# mb_01.net
KiCad netlist of a schematic drawn in EAGLE
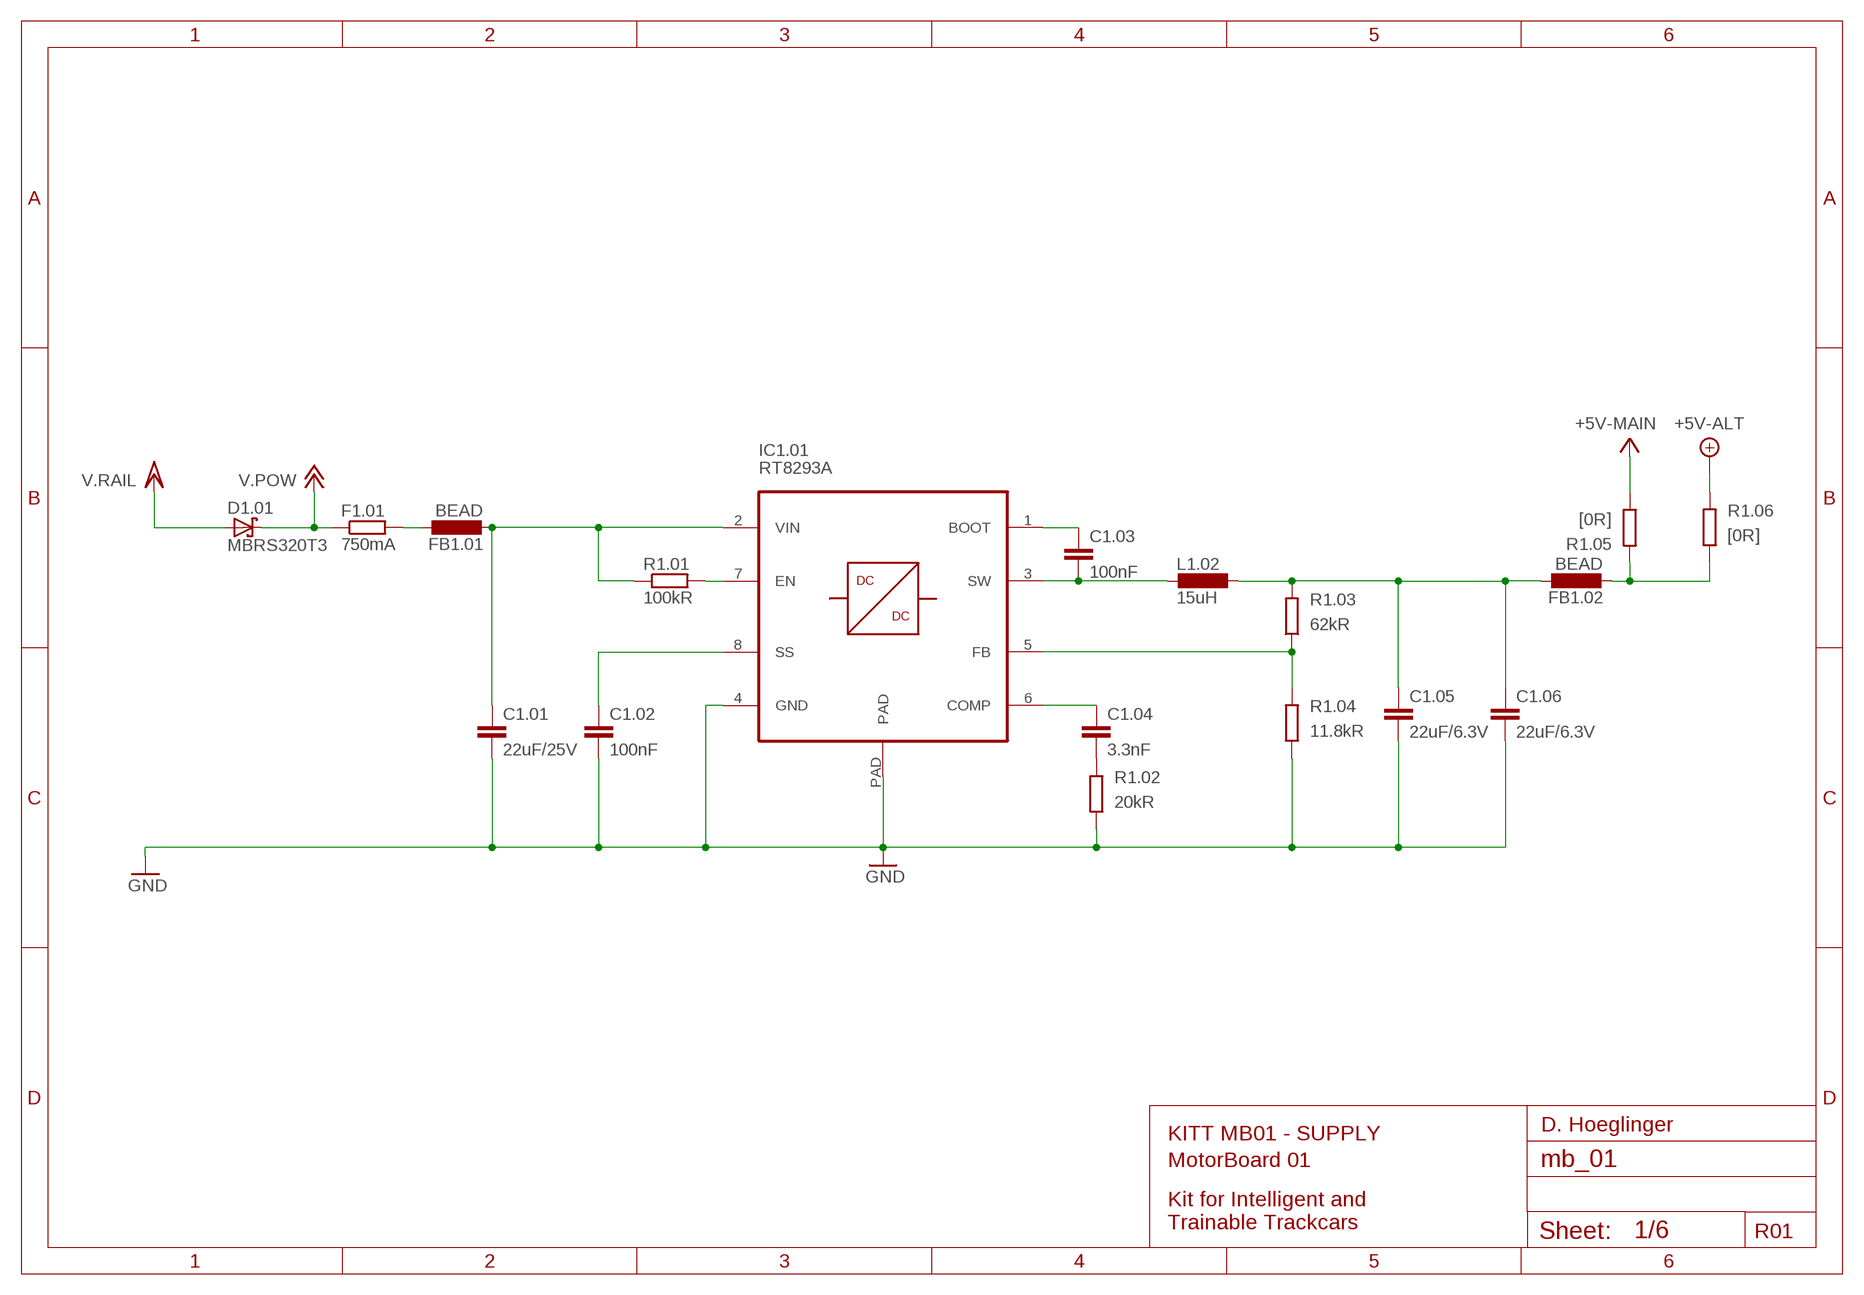
[diagram p0: schematic, sheet 1]
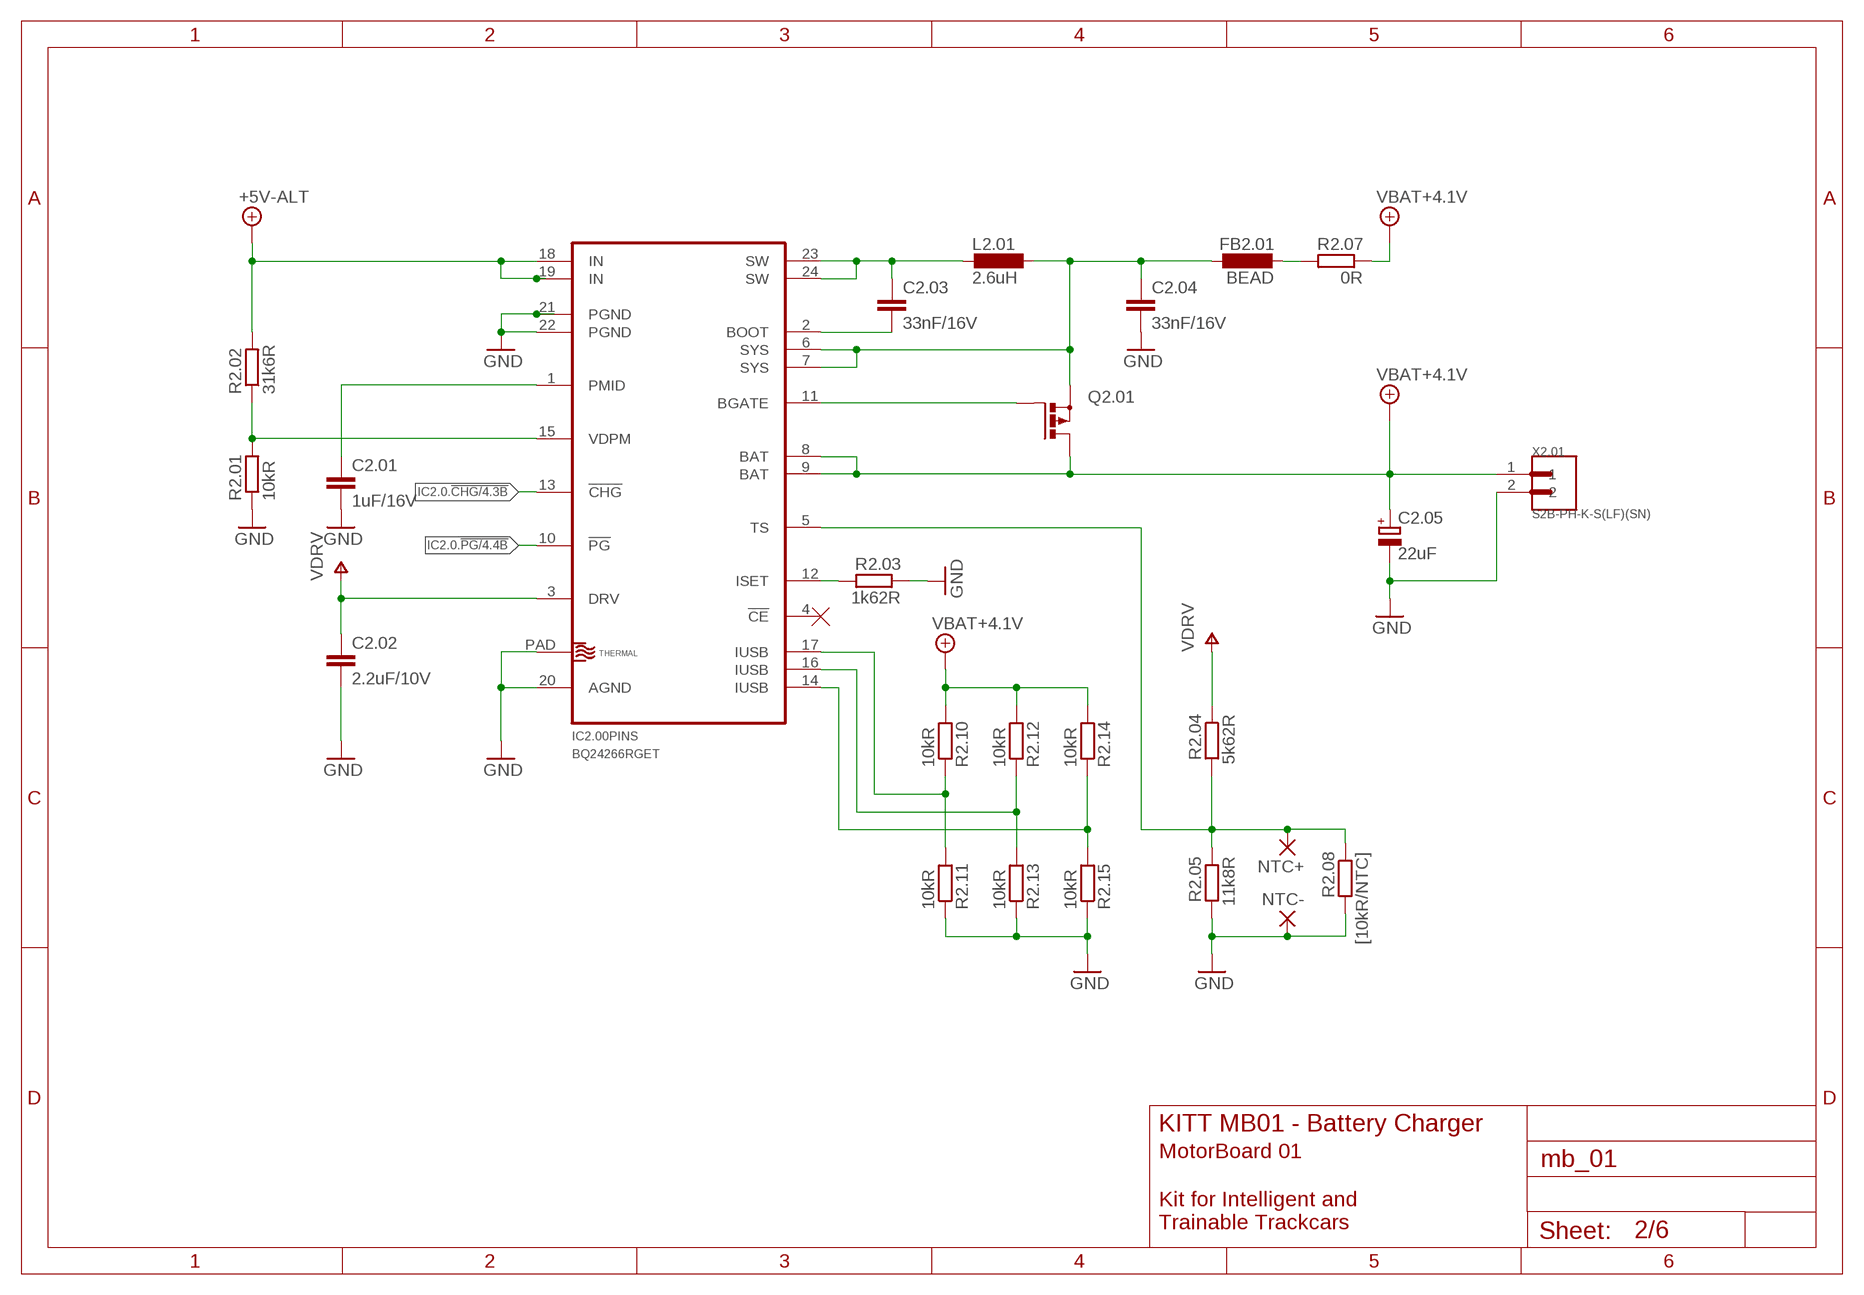
[diagram p1: schematic, sheet 2]
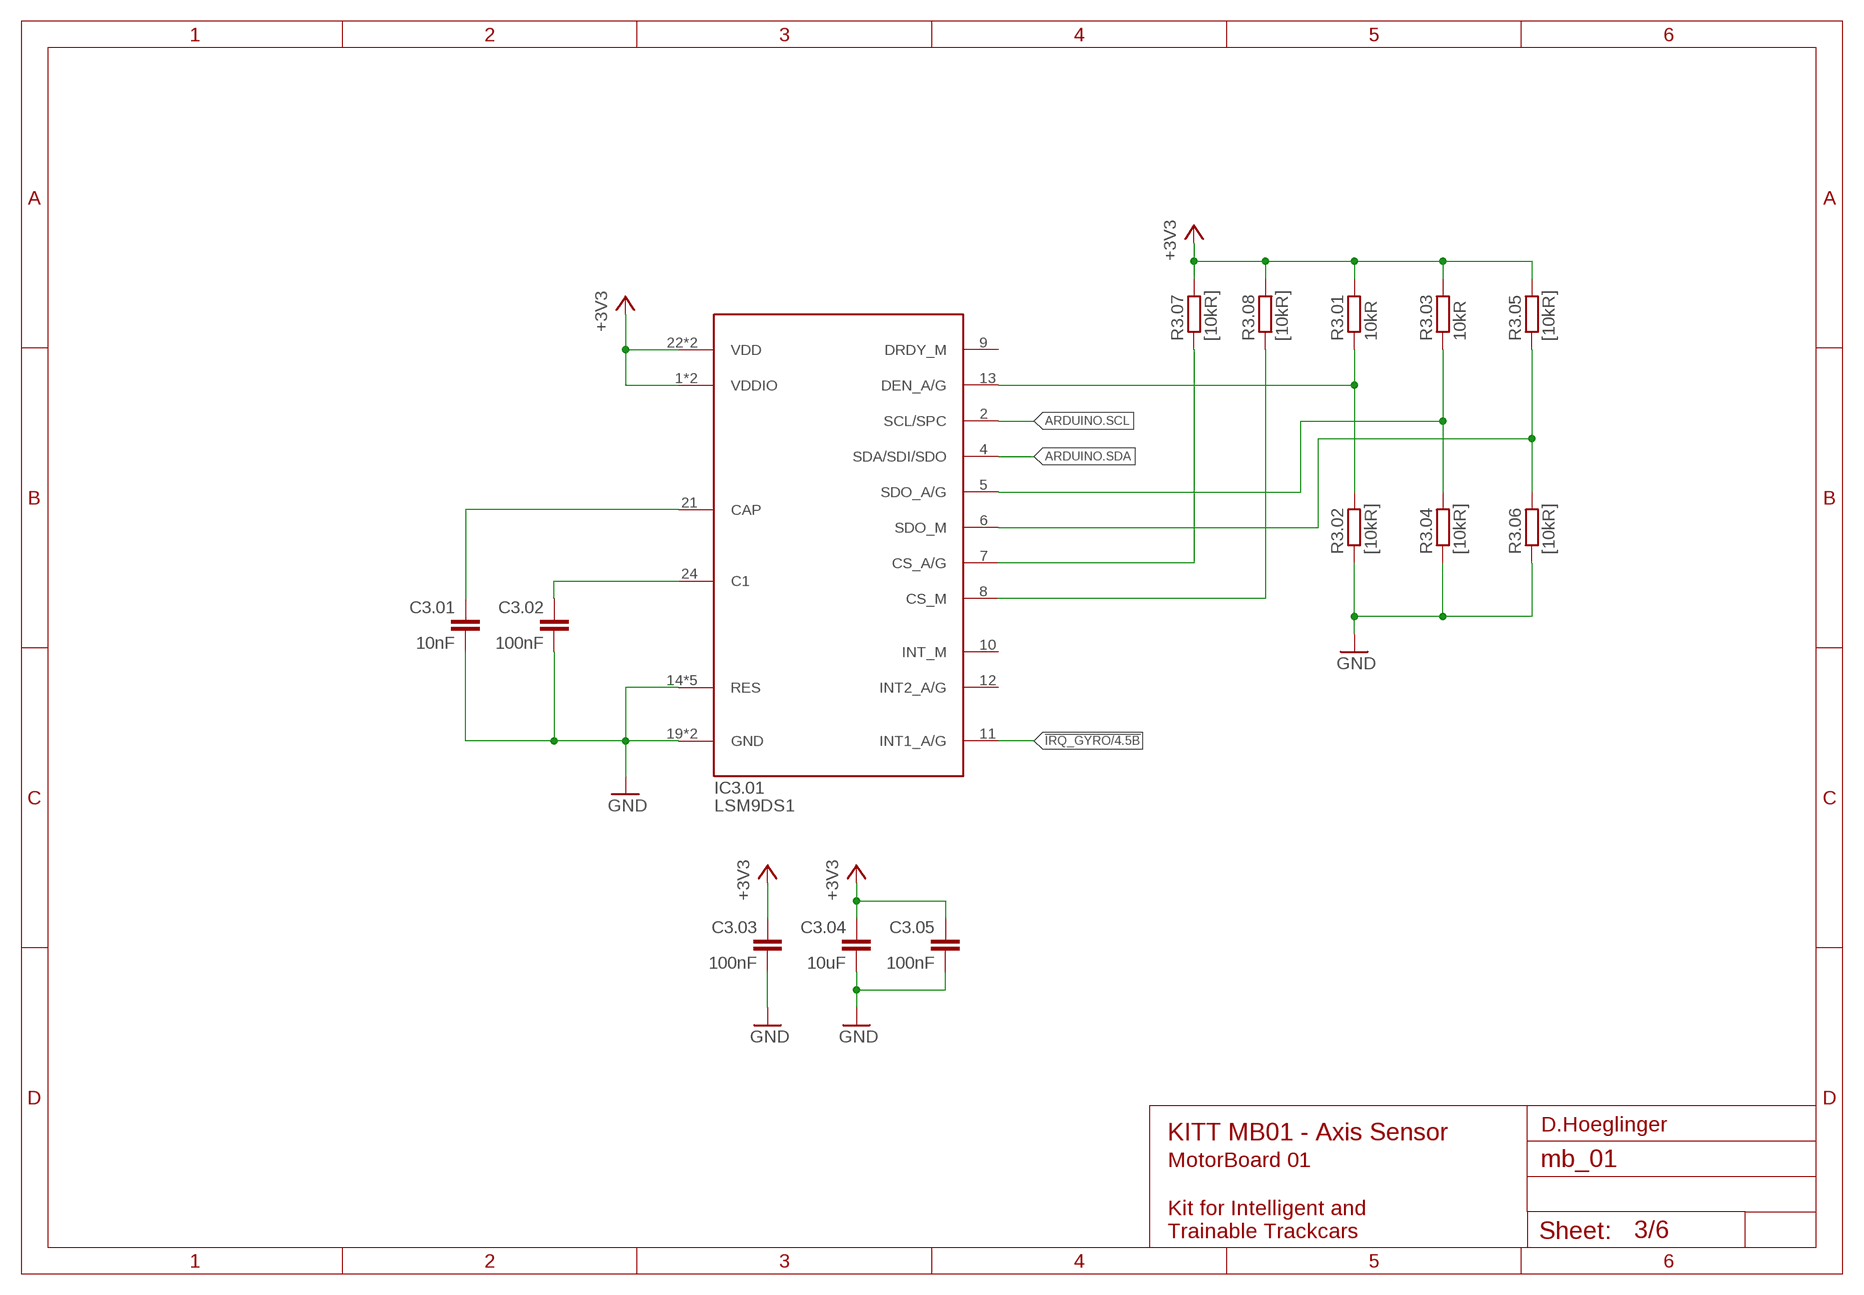
[diagram p2: schematic, sheet 3]
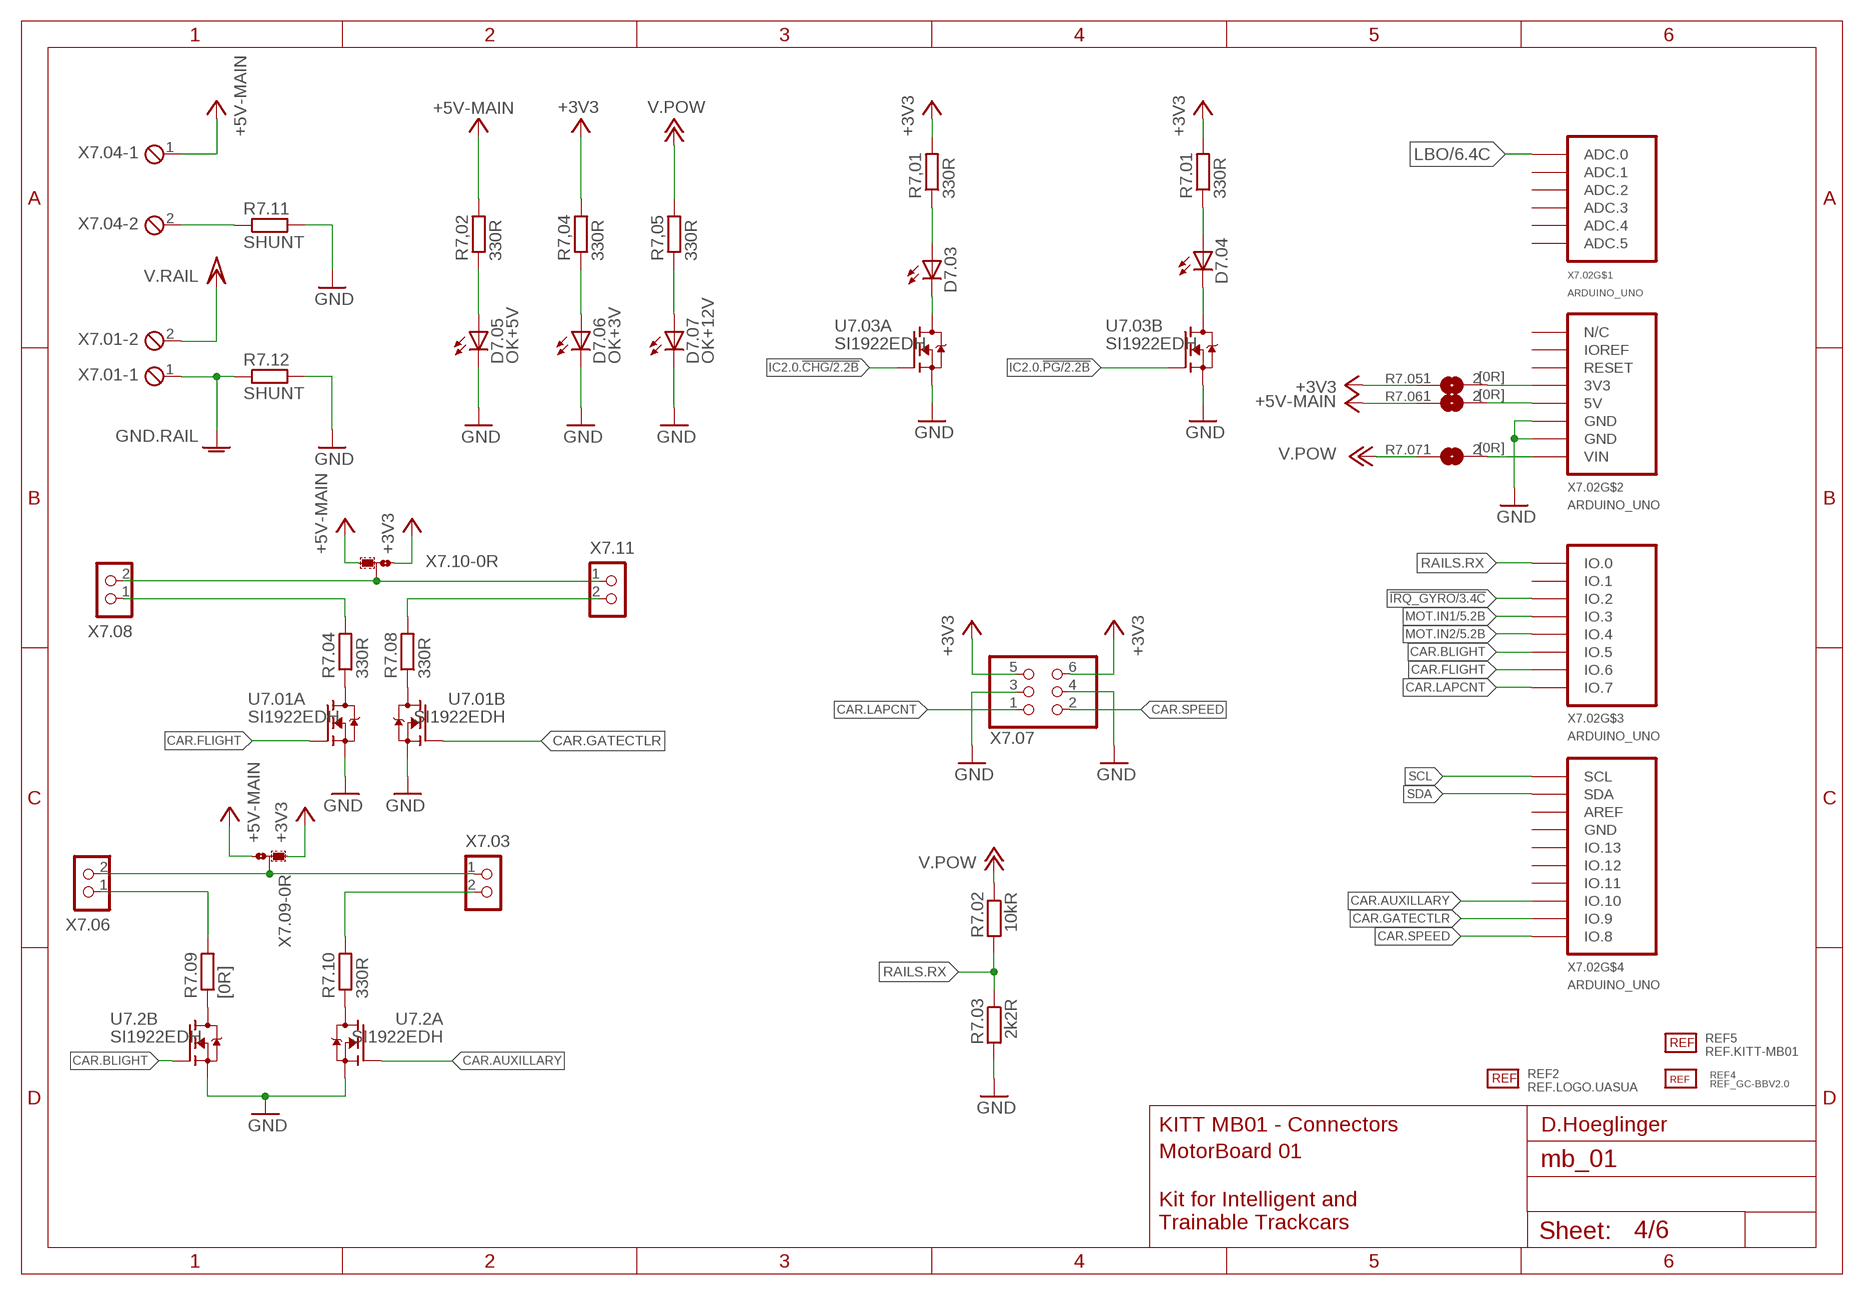
[diagram p3: schematic, sheet 4]
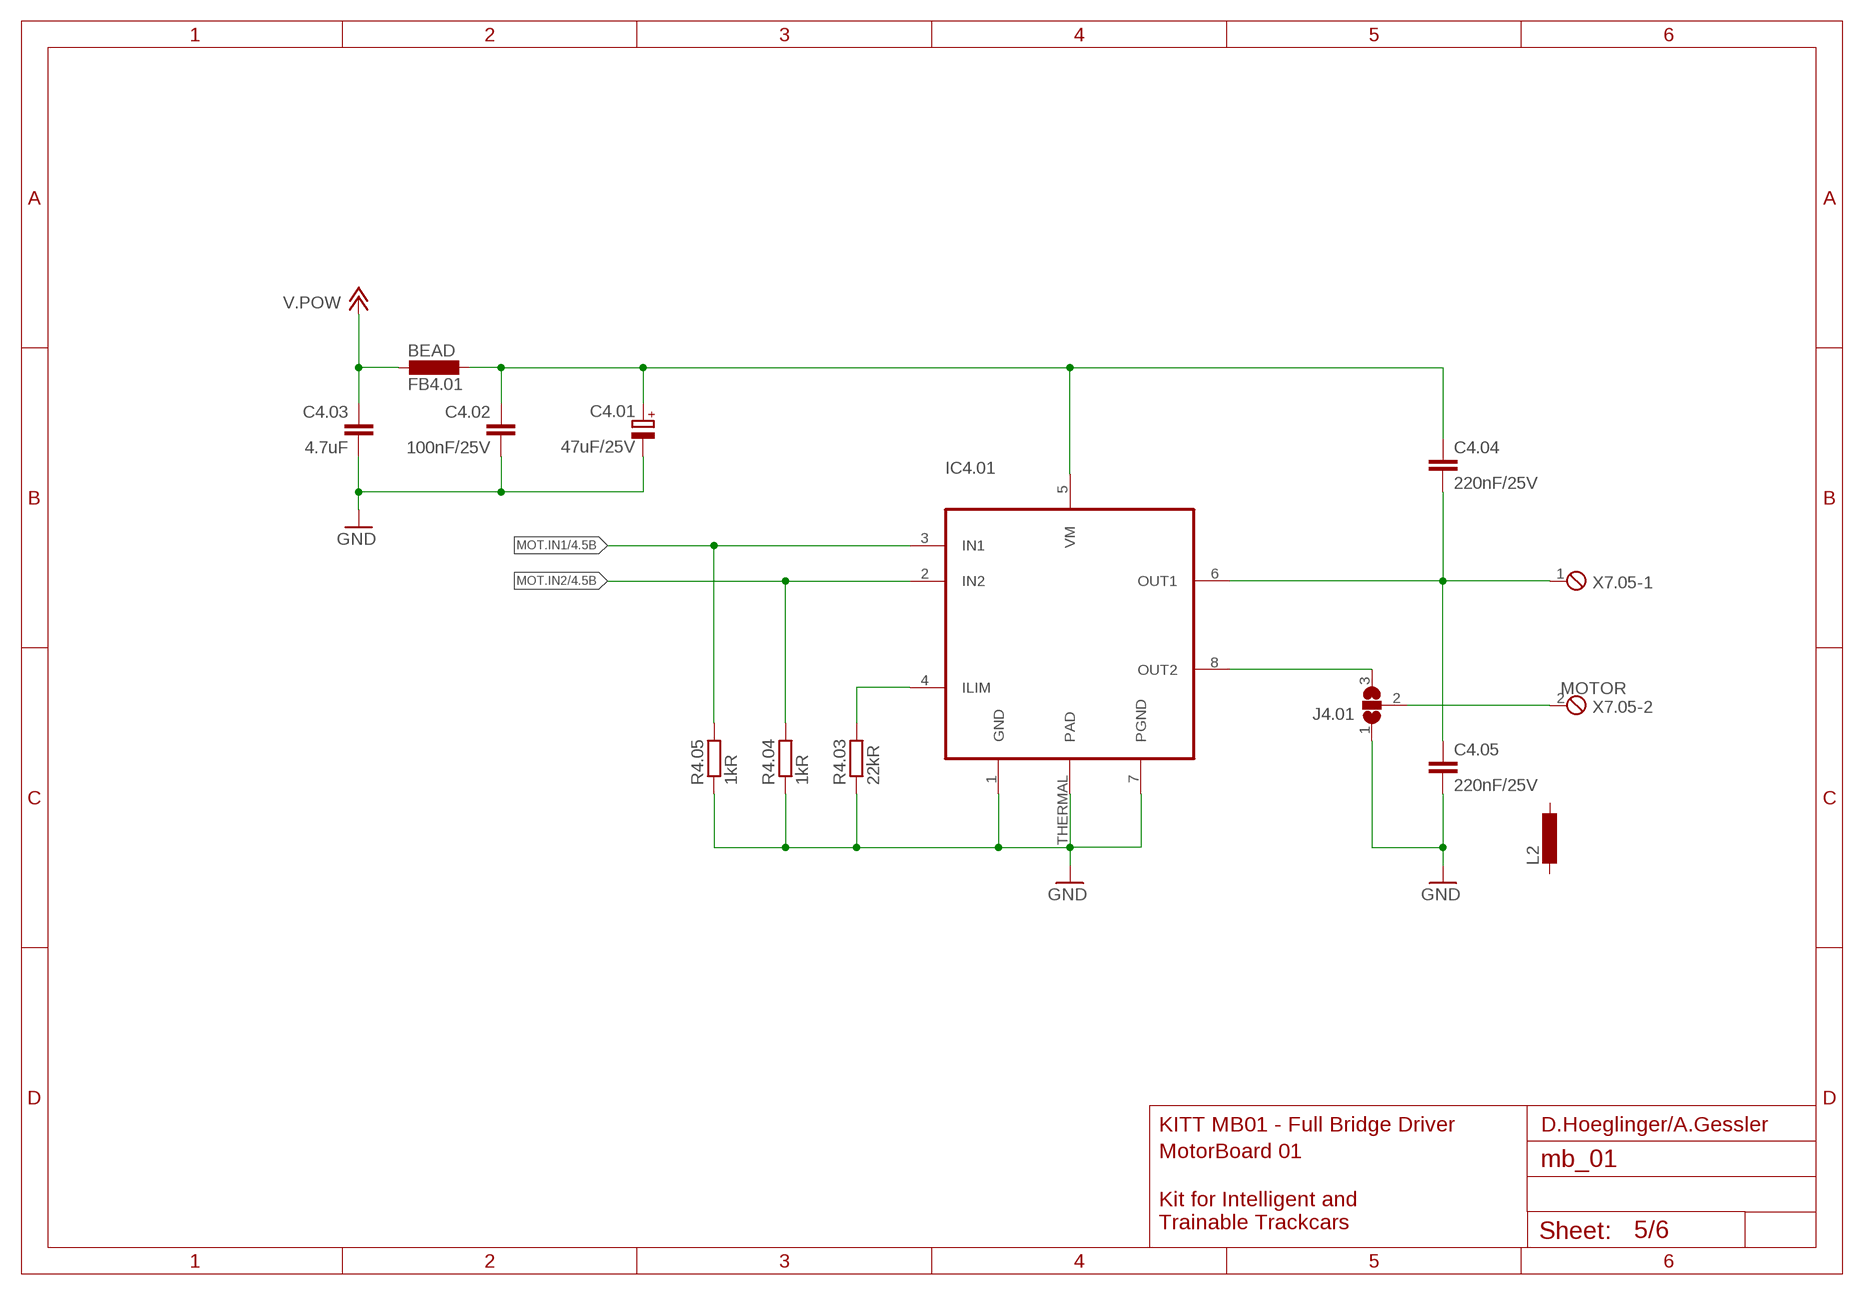
[diagram p4: schematic, sheet 5]
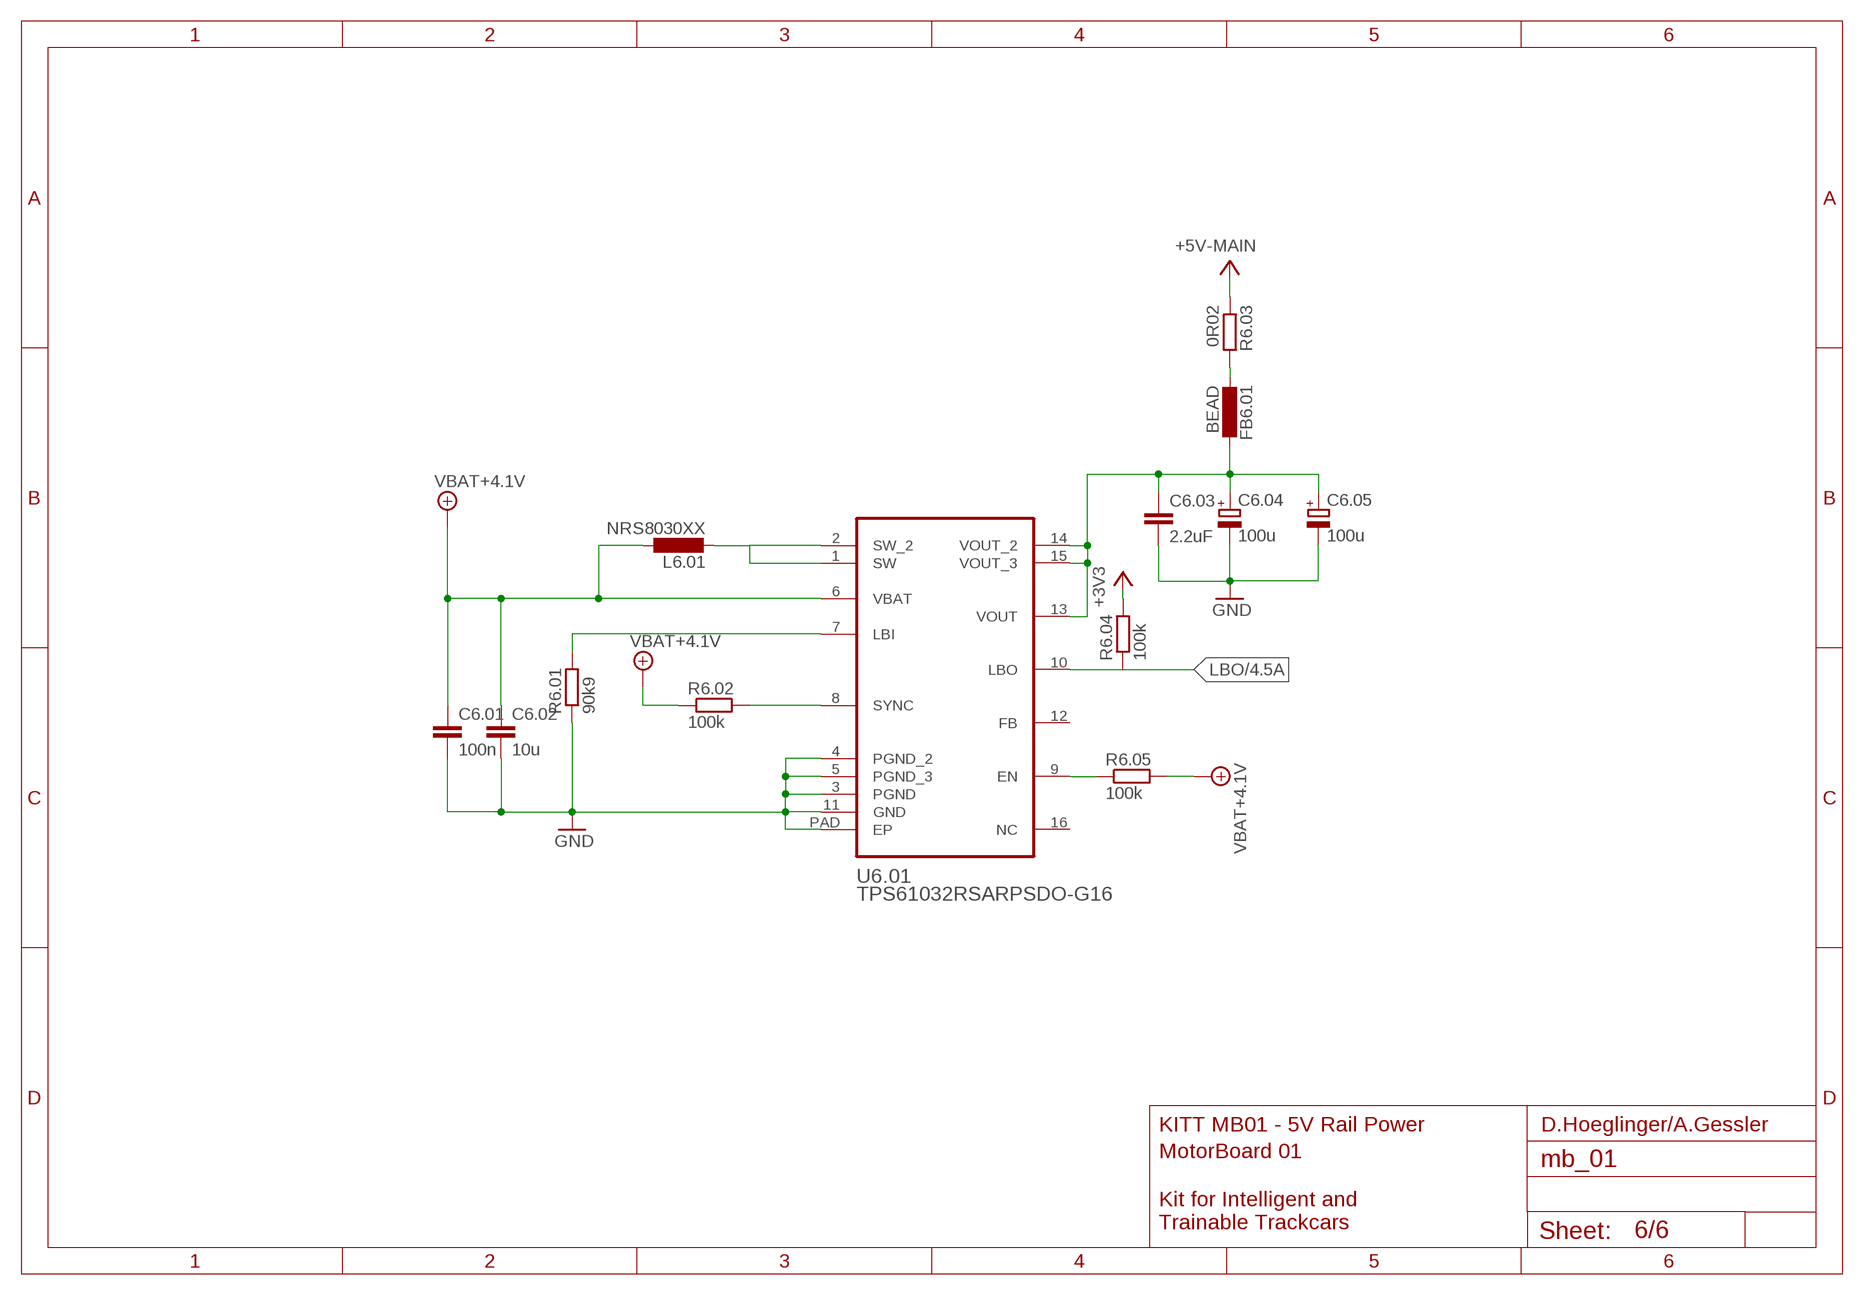
[diagram p5: schematic, sheet 6]

(export (version "E")
  (design (tool "Eeschema 10.0.6"))
  (components
    (comp (ref "C1.01")
      (value "22uF/25V")
      (footprint "eagle-import:C1210K")
      (libsource (lib "eagle-import") (part "C-EUC1210K"))
    )
    (comp (ref "C1.02")
      (value "100nF")
      (footprint "eagle-import:C0402K")
      (libsource (lib "eagle-import") (part "C-EUC0402K"))
    )
    (comp (ref "C1.03")
      (value "100nF")
      (footprint "eagle-import:C0402K")
      (libsource (lib "eagle-import") (part "C-EUC0402K"))
    )
    (comp (ref "C1.04")
      (value "3.3nF")
      (footprint "eagle-import:C0402K")
      (libsource (lib "eagle-import") (part "C-EUC0402K"))
    )
    (comp (ref "C1.05")
      (value "22uF/6.3V")
      (footprint "eagle-import:C1206K")
      (libsource (lib "eagle-import") (part "C-EUC1206K"))
    )
    (comp (ref "C1.06")
      (value "22uF/6.3V")
      (footprint "eagle-import:C1206K")
      (libsource (lib "eagle-import") (part "C-EUC1206K"))
    )
    (comp (ref "D1.01")
      (value "MBRS320T3")
      (footprint "eagle-import:SMC")
      (libsource (lib "eagle-import") (part "MBRS30T32"))
    )
    (comp (ref "F1.01")
      (value "750mA")
      (footprint "eagle-import:R1210")
      (libsource (lib "eagle-import") (part "R-EU_R1210"))
    )
    (comp (ref "FB1.01")
      (value "BEAD")
      (footprint "eagle-import:L4516C")
      (libsource (lib "eagle-import") (part "L-EUL4516C"))
    )
    (comp (ref "FB1.02")
      (value "BEAD")
      (footprint "eagle-import:L4516C")
      (libsource (lib "eagle-import") (part "L-EUL4516C"))
    )
    (comp (ref "IC1.01")
      (value "RT8293A")
      (footprint "eagle-import:SOIC-8-PAD")
      (libsource (lib "eagle-import") (part "RT8293A"))
    )
    (comp (ref "L1.02")
      (value "15uH")
      (footprint "eagle-import:TAIYO-YUDEN.NRS8030T4R7MJGJ")
      (libsource (lib "eagle-import") (part "NRS8030XX"))
    )
    (comp (ref "R1.01")
      (value "100kR")
      (footprint "eagle-import:R0402")
      (libsource (lib "eagle-import") (part "R-EU_R0402"))
    )
    (comp (ref "R1.02")
      (value "20kR")
      (footprint "eagle-import:R0402")
      (libsource (lib "eagle-import") (part "R-EU_R0402"))
    )
    (comp (ref "R1.03")
      (value "62kR")
      (footprint "eagle-import:R0402")
      (libsource (lib "eagle-import") (part "R-EU_R0402"))
    )
    (comp (ref "R1.04")
      (value "11.8kR")
      (footprint "eagle-import:R0402")
      (libsource (lib "eagle-import") (part "R-EU_R0402"))
    )
    (comp (ref "R1.05")
      (value "[0R]")
      (footprint "eagle-import:R0402")
      (libsource (lib "eagle-import") (part "R-EU_R0402"))
    )
    (comp (ref "R1.06")
      (value "[0R]")
      (footprint "eagle-import:R0402")
      (libsource (lib "eagle-import") (part "R-EU_R0402"))
    )
    (comp (ref "C2.01")
      (value "1uF/16V")
      (footprint "eagle-import:C0805")
      (libsource (lib "eagle-import") (part "C-EUC0805"))
    )
    (comp (ref "C2.02")
      (value "2.2uF/10V")
      (footprint "eagle-import:C0603K")
      (libsource (lib "eagle-import") (part "C-EUC0603K"))
    )
    (comp (ref "C2.03")
      (value "33nF/16V")
      (footprint "eagle-import:C0603")
      (libsource (lib "eagle-import") (part "C-EUC0603"))
    )
    (comp (ref "C2.04")
      (value "33nF/16V")
      (footprint "eagle-import:C0805")
      (libsource (lib "eagle-import") (part "C-EUC0805"))
    )
    (comp (ref "C2.05")
      (value "22uF")
      (footprint "eagle-import:A_3216-18R")
      (libsource (lib "eagle-import") (part "CPOL-EUA/3216-18R"))
    )
    (comp (ref "FB2.01")
      (value "BEAD")
      (footprint "eagle-import:L4516C")
      (libsource (lib "eagle-import") (part "L-EUL4516C"))
    )
    (comp (ref "IC2.00")
      (value "BQ24266RGET")
      (footprint "eagle-import:VQFN-24")
      (libsource (lib "eagle-import") (part "BQ24266RGET"))
    )
    (comp (ref "L2.01")
      (value "2.6uH")
      (footprint "eagle-import:TAIYO-YUDEN.NRS8030T4R7MJGJ")
      (libsource (lib "eagle-import") (part "NRS8030XX"))
    )
    (comp (ref "NTC+")
      (value "SMD2")
      (footprint "eagle-import:SMD1,27-2,54")
      (libsource (lib "eagle-import") (part "SMD2"))
    )
    (comp (ref "NTC-")
      (value "SMD2")
      (footprint "eagle-import:SMD1,27-2,54")
      (libsource (lib "eagle-import") (part "SMD2"))
    )
    (comp (ref "Q2.01")
      (value "P-MOSFET-SO8")
      (footprint "eagle-import:SO-08")
      (libsource (lib "eagle-import") (part "P-MOSFET-SO8"))
    )
    (comp (ref "R2.01")
      (value "10kR")
      (footprint "eagle-import:R0402")
      (libsource (lib "eagle-import") (part "R-EU_R0402"))
    )
    (comp (ref "R2.02")
      (value "31k6R")
      (footprint "eagle-import:R0402")
      (libsource (lib "eagle-import") (part "R-EU_R0402"))
    )
    (comp (ref "R2.03")
      (value "1k62R")
      (footprint "eagle-import:R0402")
      (libsource (lib "eagle-import") (part "R-EU_R0402"))
    )
    (comp (ref "R2.04")
      (value "5k62R")
      (footprint "eagle-import:R0402")
      (libsource (lib "eagle-import") (part "R-EU_R0402"))
    )
    (comp (ref "R2.05")
      (value "11k8R")
      (footprint "eagle-import:R0402")
      (libsource (lib "eagle-import") (part "R-EU_R0402"))
    )
    (comp (ref "R2.07")
      (value "0R")
      (footprint "eagle-import:R0402")
      (libsource (lib "eagle-import") (part "R-EU_R0402"))
    )
    (comp (ref "R2.08")
      (value "[10kR/NTC]")
      (footprint "eagle-import:R0402")
      (libsource (lib "eagle-import") (part "R-EU_R0402"))
    )
    (comp (ref "R2.10")
      (value "10kR")
      (footprint "eagle-import:R0402")
      (libsource (lib "eagle-import") (part "R-EU_R0402"))
    )
    (comp (ref "R2.11")
      (value "10kR")
      (footprint "eagle-import:R0402")
      (libsource (lib "eagle-import") (part "R-EU_R0402"))
    )
    (comp (ref "R2.12")
      (value "10kR")
      (footprint "eagle-import:R0402")
      (libsource (lib "eagle-import") (part "R-EU_R0402"))
    )
    (comp (ref "R2.13")
      (value "10kR")
      (footprint "eagle-import:R0402")
      (libsource (lib "eagle-import") (part "R-EU_R0402"))
    )
    (comp (ref "R2.14")
      (value "10kR")
      (footprint "eagle-import:R0402")
      (libsource (lib "eagle-import") (part "R-EU_R0402"))
    )
    (comp (ref "R2.15")
      (value "10kR")
      (footprint "eagle-import:R0402")
      (libsource (lib "eagle-import") (part "R-EU_R0402"))
    )
    (comp (ref "X2.01")
      (value "S2B-PH-K-S(LF)(SN)")
      (footprint "eagle-import:JST_S2B-PH-K-S(LF)(SN)")
      (fields (field (name "MF") "JST"))
      (libsource (lib "eagle-import") (part "S2B-PH-K-S(LF)(SN)"))
    )
    (comp (ref "D7.03")
      (value "LEDCHIPLED_1206")
      (footprint "eagle-import:CHIPLED_1206")
      (libsource (lib "eagle-import") (part "LEDCHIPLED_1206"))
    )
    (comp (ref "D7.04")
      (value "LEDCHIPLED_1206")
      (footprint "eagle-import:CHIPLED_1206")
      (libsource (lib "eagle-import") (part "LEDCHIPLED_1206"))
    )
    (comp (ref "D7.05")
      (value "OK+5V")
      (footprint "eagle-import:CHIPLED_1206")
      (libsource (lib "eagle-import") (part "LEDCHIPLED_1206"))
    )
    (comp (ref "D7.06")
      (value "OK+3V")
      (footprint "eagle-import:CHIPLED_1206")
      (libsource (lib "eagle-import") (part "LEDCHIPLED_1206"))
    )
    (comp (ref "D7.07")
      (value "OK+12V")
      (footprint "eagle-import:CHIPLED_1206")
      (libsource (lib "eagle-import") (part "LEDCHIPLED_1206"))
    )
    (comp (ref "R7,01")
      (value "330R")
      (footprint "eagle-import:R0603")
      (libsource (lib "eagle-import") (part "R-EU_R0603"))
    )
    (comp (ref "R7,02")
      (value "330R")
      (footprint "eagle-import:R0603")
      (libsource (lib "eagle-import") (part "R-EU_R0603"))
    )
    (comp (ref "R7,04")
      (value "330R")
      (footprint "eagle-import:R0603")
      (libsource (lib "eagle-import") (part "R-EU_R0603"))
    )
    (comp (ref "R7,05")
      (value "330R")
      (footprint "eagle-import:R0603")
      (libsource (lib "eagle-import") (part "R-EU_R0603"))
    )
    (comp (ref "R7.01")
      (value "330R")
      (footprint "eagle-import:R0603")
      (libsource (lib "eagle-import") (part "R-EU_R0603"))
    )
    (comp (ref "R7.02")
      (value "10kR")
      (footprint "eagle-import:M0805")
      (libsource (lib "eagle-import") (part "R-EU_M0805"))
    )
    (comp (ref "R7.03")
      (value "2k2R")
      (footprint "eagle-import:M0805")
      (libsource (lib "eagle-import") (part "R-EU_M0805"))
    )
    (comp (ref "R7.04")
      (value "330R")
      (footprint "eagle-import:R0603")
      (libsource (lib "eagle-import") (part "R-EU_R0603"))
    )
    (comp (ref "R7.05")
      (value "[0R]")
      (footprint "eagle-import:SJ")
      (libsource (lib "eagle-import") (part "SJ"))
    )
    (comp (ref "R7.06")
      (value "[0R]")
      (footprint "eagle-import:SJ")
      (libsource (lib "eagle-import") (part "SJ"))
    )
    (comp (ref "R7.07")
      (value "[0R]")
      (footprint "eagle-import:SJ")
      (libsource (lib "eagle-import") (part "SJ"))
    )
    (comp (ref "R7.08")
      (value "330R")
      (footprint "eagle-import:R0603")
      (libsource (lib "eagle-import") (part "R-EU_R0603"))
    )
    (comp (ref "R7.09")
      (value "[0R]")
      (footprint "eagle-import:R0603")
      (libsource (lib "eagle-import") (part "R-EU_R0603"))
    )
    (comp (ref "R7.10")
      (value "330R")
      (footprint "eagle-import:R0603")
      (libsource (lib "eagle-import") (part "R-EU_R0603"))
    )
    (comp (ref "R7.11")
      (value "SHUNT")
      (footprint "eagle-import:R1206")
      (libsource (lib "eagle-import") (part "R-EU_R1206"))
    )
    (comp (ref "R7.12")
      (value "SHUNT")
      (footprint "eagle-import:R1206")
      (libsource (lib "eagle-import") (part "R-EU_R1206"))
    )
    (comp (ref "REF2")
      (value "REF.LOGO.UASUA")
      (footprint "eagle-import:REF_LOGO_UASUA")
      (libsource (lib "eagle-import") (part "REF.LOGO.UASUA"))
    )
    (comp (ref "REF4")
      (value "REF_GC-BBV2.0")
      (footprint "eagle-import:REF_GHOSTCAR")
      (libsource (lib "eagle-import") (part "REF_GC-BBV2.0"))
    )
    (comp (ref "REF5")
      (value "REF.KITT-MB01")
      (footprint "eagle-import:REF_KITT_MB01")
      (libsource (lib "eagle-import") (part "REF.KITT-MB01"))
    )
    (comp (ref "U7.01")
      (value "SI1922EDH")
      (footprint "eagle-import:SC70-6")
      (libsource (lib "eagle-import") (part "SI1922EDH"))
    )
    (comp (ref "U7.2")
      (value "SI1922EDH")
      (footprint "eagle-import:SC70-6")
      (libsource (lib "eagle-import") (part "SI1922EDH"))
    )
    (comp (ref "U7.03")
      (value "SI1922EDH")
      (footprint "eagle-import:SC70-6")
      (libsource (lib "eagle-import") (part "SI1922EDH"))
    )
    (comp (ref "X7.01")
      (value "MPT2")
      (footprint "eagle-import:2POL254")
      (libsource (lib "eagle-import") (part "MPT2"))
    )
    (comp (ref "X7.02")
      (value "ARDUINO_UNO")
      (footprint "eagle-import:AU_PINS")
      (libsource (lib "eagle-import") (part "ARDUINO_UNO"))
    )
    (comp (ref "X7.03")
      (value "CON_HEADER_1X02")
      (footprint "eagle-import:M1X2_MALE_RIGHT_ANGLED_SMD")
      (libsource (lib "eagle-import") (part "CON_HEADER_1X02"))
    )
    (comp (ref "X7.04")
      (value "MPT2")
      (footprint "eagle-import:2POL254")
      (libsource (lib "eagle-import") (part "MPT2"))
    )
    (comp (ref "X7.06")
      (value "CON_HEADER_1X02")
      (footprint "eagle-import:M1X2_MALE_RIGHT_ANGLED_SMD")
      (libsource (lib "eagle-import") (part "CON_HEADER_1X02"))
    )
    (comp (ref "X7.07")
      (value "PINHD-2X3/90")
      (footprint "eagle-import:2X03_90")
      (libsource (lib "eagle-import") (part "PINHD-2X3/90"))
    )
    (comp (ref "X7.08")
      (value "CON_HEADER_1X02")
      (footprint "eagle-import:M1X2_MALE_RIGHT_ANGLED_SMD")
      (libsource (lib "eagle-import") (part "CON_HEADER_1X02"))
    )
    (comp (ref "X7.09")
      (value "0R-JUMPA")
      (footprint "eagle-import:A0R-JMP")
      (libsource (lib "eagle-import") (part "0R-JUMPA"))
    )
    (comp (ref "X7.10")
      (value "0R-JUMPA")
      (footprint "eagle-import:A0R-JMP")
      (libsource (lib "eagle-import") (part "0R-JUMPA"))
    )
    (comp (ref "X7.11")
      (value "CON_HEADER_1X02")
      (footprint "eagle-import:M1X2_MALE_RIGHT_ANGLED_SMD")
      (libsource (lib "eagle-import") (part "CON_HEADER_1X02"))
    )
    (comp (ref "C3.01")
      (value "10nF")
      (footprint "eagle-import:C0603")
      (libsource (lib "eagle-import") (part "C-EUC0603"))
    )
    (comp (ref "C3.02")
      (value "100nF")
      (footprint "eagle-import:C0402")
      (libsource (lib "eagle-import") (part "C-EUC0402"))
    )
    (comp (ref "C3.03")
      (value "100nF")
      (footprint "eagle-import:C0402")
      (libsource (lib "eagle-import") (part "C-EUC0402"))
    )
    (comp (ref "C3.04")
      (value "10uF")
      (footprint "eagle-import:C0603K")
      (libsource (lib "eagle-import") (part "resistor_C-EUC0603K"))
    )
    (comp (ref "C3.05")
      (value "100nF")
      (footprint "eagle-import:C0402")
      (libsource (lib "eagle-import") (part "C-EUC0402"))
    )
    (comp (ref "IC3.01")
      (value "LSM9DS1")
      (footprint "eagle-import:LGA-24")
      (fields (field (name "MF") "STMicroelectronics"))
      (libsource (lib "eagle-import") (part "LSM9DS1"))
    )
    (comp (ref "R3.01")
      (value "10kR")
      (footprint "eagle-import:R0402")
      (libsource (lib "eagle-import") (part "R-EU_R0402"))
    )
    (comp (ref "R3.02")
      (value "[10kR]")
      (footprint "eagle-import:R0402")
      (libsource (lib "eagle-import") (part "R-EU_R0402"))
    )
    (comp (ref "R3.03")
      (value "10kR")
      (footprint "eagle-import:R0402")
      (libsource (lib "eagle-import") (part "R-EU_R0402"))
    )
    (comp (ref "R3.04")
      (value "[10kR]")
      (footprint "eagle-import:R0402")
      (libsource (lib "eagle-import") (part "R-EU_R0402"))
    )
    (comp (ref "R3.05")
      (value "[10kR]")
      (footprint "eagle-import:R0402")
      (libsource (lib "eagle-import") (part "R-EU_R0402"))
    )
    (comp (ref "R3.06")
      (value "[10kR]")
      (footprint "eagle-import:R0402")
      (libsource (lib "eagle-import") (part "R-EU_R0402"))
    )
    (comp (ref "R3.07")
      (value "[10kR]")
      (footprint "eagle-import:R0402")
      (libsource (lib "eagle-import") (part "R-EU_R0402"))
    )
    (comp (ref "R3.08")
      (value "[10kR]")
      (footprint "eagle-import:R0402")
      (libsource (lib "eagle-import") (part "R-EU_R0402"))
    )
    (comp (ref "C6.01")
      (value "100n")
      (footprint "eagle-import:C0402")
      (libsource (lib "eagle-import") (part "C-EUC0402"))
    )
    (comp (ref "C6.02")
      (value "10u")
      (footprint "eagle-import:C0603")
      (libsource (lib "eagle-import") (part "C-EUC0603"))
    )
    (comp (ref "C6.03")
      (value "2.2uF")
      (footprint "eagle-import:C0603")
      (libsource (lib "eagle-import") (part "C-EUC0603"))
    )
    (comp (ref "C6.04")
      (value "100u")
      (footprint "eagle-import:C-2312")
      (libsource (lib "eagle-import") (part "CPOL-29172312"))
    )
    (comp (ref "C6.05")
      (value "100u")
      (footprint "eagle-import:C-2312")
      (libsource (lib "eagle-import") (part "CPOL-29172312"))
    )
    (comp (ref "FB6.01")
      (value "BEAD")
      (footprint "eagle-import:L4516C")
      (libsource (lib "eagle-import") (part "L-EUL4516C"))
    )
    (comp (ref "L6.01")
      (value "NRS8030XX")
      (footprint "eagle-import:TAIYO-YUDEN.NRS8030T4R7MJGJ")
      (libsource (lib "eagle-import") (part "NRS8030XX"))
    )
    (comp (ref "R6.01")
      (value "90k9")
      (footprint "eagle-import:R0402")
      (libsource (lib "eagle-import") (part "R-EU_R0402"))
    )
    (comp (ref "R6.02")
      (value "100k")
      (footprint "eagle-import:R0402")
      (libsource (lib "eagle-import") (part "R-EU_R0402"))
    )
    (comp (ref "R6.03")
      (value "0R02")
      (footprint "eagle-import:R0805")
      (libsource (lib "eagle-import") (part "R-EU_R0805"))
    )
    (comp (ref "R6.04")
      (value "100k")
      (footprint "eagle-import:R0402")
      (libsource (lib "eagle-import") (part "R-EU_R0402"))
    )
    (comp (ref "R6.05")
      (value "100k")
      (footprint "eagle-import:R0402")
      (libsource (lib "eagle-import") (part "R-EU_R0402"))
    )
    (comp (ref "U6.01")
      (value "TPS61032RSARPSDO-G16")
      (footprint "eagle-import:R-PDSO-G16")
      (libsource (lib "eagle-import") (part "TPS61032RSARPSDO-G16"))
    )
    (comp (ref "C4.01")
      (value "47uF/25V")
      (footprint "eagle-import:C_6032-28R")
      (libsource (lib "eagle-import") (part "CPOL-EUC/6032-28R"))
    )
    (comp (ref "C4.02")
      (value "100nF/25V")
      (footprint "eagle-import:C0603K")
      (libsource (lib "eagle-import") (part "resistor_C-EUC0603K"))
    )
    (comp (ref "C4.03")
      (value "4.7uF")
      (footprint "eagle-import:C0805K")
      (libsource (lib "eagle-import") (part "resistor_C-EUC0805K"))
    )
    (comp (ref "C4.04")
      (value "220nF/25V")
      (footprint "eagle-import:C0603K")
      (libsource (lib "eagle-import") (part "C-EUC0603K"))
    )
    (comp (ref "C4.05")
      (value "220nF/25V")
      (footprint "eagle-import:C0603K")
      (libsource (lib "eagle-import") (part "C-EUC0603K"))
    )
    (comp (ref "FB4.01")
      (value "BEAD")
      (footprint "eagle-import:L4516C")
      (libsource (lib "eagle-import") (part "L-EUL4516C"))
    )
    (comp (ref "IC4.01")
      (value "DRV8871")
      (footprint "eagle-import:HSOP8")
      (libsource (lib "eagle-import") (part "DRV8871"))
    )
    (comp (ref "J4.01")
      (value "SJ2W")
      (footprint "eagle-import:SJ_2")
      (libsource (lib "eagle-import") (part "SJ2W"))
    )
    (comp (ref "L2")
      (value "L-EUL4516C")
      (footprint "eagle-import:L4516C")
      (libsource (lib "eagle-import") (part "L-EUL4516C"))
    )
    (comp (ref "R4.03")
      (value "22kR")
      (footprint "eagle-import:R0402")
      (libsource (lib "eagle-import") (part "resistor_R-EU_R0402"))
    )
    (comp (ref "R4.04")
      (value "1kR")
      (footprint "eagle-import:R0402")
      (libsource (lib "eagle-import") (part "resistor_R-EU_R0402"))
    )
    (comp (ref "R4.05")
      (value "1kR")
      (footprint "eagle-import:R0402")
      (libsource (lib "eagle-import") (part "resistor_R-EU_R0402"))
    )
    (comp (ref "X7.05")
      (value "MOTOR")
      (footprint "eagle-import:2POL254")
      (libsource (lib "eagle-import") (part "MPT2"))
    )
  )
  (nets
    (net (code "1") (name "+3V3") (class "Default")
      (node (ref "C3.03") (pin "1") (pinfunction "1_1") (pintype "passive"))
      (node (ref "C3.04") (pin "1") (pinfunction "1_1") (pintype "passive"))
      (node (ref "C3.05") (pin "1") (pinfunction "1_1") (pintype "passive"))
      (node (ref "IC3.01") (pin "1") (pinfunction "VDDIO_1") (pintype "bidirectional"))
      (node (ref "IC3.01") (pin "22") (pinfunction "VDD_22") (pintype "bidirectional"))
      (node (ref "IC3.01") (pin "23") (pinfunction "VDD_23") (pintype "bidirectional"))
      (node (ref "IC3.01") (pin "3") (pinfunction "VDDIO_3") (pintype "bidirectional"))
      (node (ref "R3.01") (pin "2") (pinfunction "2_2") (pintype "passive"))
      (node (ref "R3.03") (pin "2") (pinfunction "2_2") (pintype "passive"))
      (node (ref "R3.05") (pin "2") (pinfunction "2_2") (pintype "passive"))
      (node (ref "R3.07") (pin "2") (pinfunction "2_2") (pintype "passive"))
      (node (ref "R3.08") (pin "2") (pinfunction "2_2") (pintype "passive"))
      (node (ref "R6.04") (pin "2") (pinfunction "2_2") (pintype "passive"))
      (node (ref "R7,01") (pin "2") (pinfunction "2_2") (pintype "passive"))
      (node (ref "R7,04") (pin "2") (pinfunction "2_2") (pintype "passive"))
      (node (ref "R7.01") (pin "2") (pinfunction "2_2") (pintype "passive"))
      (node (ref "R7.05") (pin "1") (pinfunction "1_1") (pintype "passive"))
      (node (ref "X7.07") (pin "5") (pinfunction "5_5") (pintype "passive"))
      (node (ref "X7.07") (pin "6") (pinfunction "6_6") (pintype "passive"))
      (node (ref "X7.09") (pin "1") (pinfunction "1_1") (pintype "passive"))
      (node (ref "X7.10") (pin "1") (pinfunction "1_1") (pintype "passive"))
    )
    (net (code "2") (name "+4.1V") (class "Default")
      (node (ref "C2.05") (pin "+") (pinfunction "+_+") (pintype "passive"))
      (node (ref "C6.01") (pin "1") (pinfunction "1_1") (pintype "passive"))
      (node (ref "C6.02") (pin "1") (pinfunction "1_1") (pintype "passive"))
      (node (ref "IC2.00") (pin "8") (pinfunction "BAT_8") (pintype "bidirectional"))
      (node (ref "IC2.00") (pin "9") (pinfunction "BAT_9") (pintype "bidirectional"))
      (node (ref "L6.01") (pin "1") (pinfunction "1_1") (pintype "passive"))
      (node (ref "Q2.01") (pin "5") (pinfunction "D_5") (pintype "passive"))
      (node (ref "Q2.01") (pin "6") (pinfunction "D_6") (pintype "passive"))
      (node (ref "Q2.01") (pin "7") (pinfunction "D_7") (pintype "passive"))
      (node (ref "Q2.01") (pin "8") (pinfunction "D_8") (pintype "passive"))
      (node (ref "R2.07") (pin "1") (pinfunction "1_1") (pintype "passive"))
      (node (ref "R2.10") (pin "2") (pinfunction "2_2") (pintype "passive"))
      (node (ref "R2.12") (pin "2") (pinfunction "2_2") (pintype "passive"))
      (node (ref "R2.14") (pin "2") (pinfunction "2_2") (pintype "passive"))
      (node (ref "R6.02") (pin "1") (pinfunction "1_1") (pintype "passive"))
      (node (ref "R6.05") (pin "2") (pinfunction "2_2") (pintype "passive"))
      (node (ref "U6.01") (pin "6") (pinfunction "VBAT_6") (pintype "input"))
      (node (ref "X2.01") (pin "1") (pinfunction "1_1") (pintype "passive"))
    )
    (net (code "3") (name "+5V") (class "Default")
      (node (ref "IC2.00") (pin "18") (pinfunction "IN_18") (pintype "bidirectional"))
      (node (ref "IC2.00") (pin "19") (pinfunction "IN_19") (pintype "bidirectional"))
      (node (ref "R1.05") (pin "1") (pinfunction "1_1") (pintype "passive"))
      (node (ref "R1.06") (pin "2") (pinfunction "2_2") (pintype "passive"))
      (node (ref "R2.02") (pin "2") (pinfunction "2_2") (pintype "passive"))
      (node (ref "R6.03") (pin "1") (pinfunction "1_1") (pintype "passive"))
      (node (ref "R7,02") (pin "2") (pinfunction "2_2") (pintype "passive"))
      (node (ref "R7.06") (pin "1") (pinfunction "1_1") (pintype "passive"))
      (node (ref "X7.04") (pin "1") (pinfunction "1_1") (pintype "passive"))
      (node (ref "X7.09") (pin "3") (pinfunction "3_3") (pintype "passive"))
      (node (ref "X7.10") (pin "3") (pinfunction "3_3") (pintype "passive"))
    )
    (net (code "4") (name "+12V") (class "Default")
      (node (ref "C4.03") (pin "1") (pinfunction "1_1") (pintype "passive"))
      (node (ref "D1.01") (pin "C") (pinfunction "C_C") (pintype "passive"))
      (node (ref "F1.01") (pin "1") (pinfunction "1_1") (pintype "passive"))
      (node (ref "FB4.01") (pin "2") (pinfunction "2_2") (pintype "passive"))
      (node (ref "R7,05") (pin "2") (pinfunction "2_2") (pintype "passive"))
      (node (ref "R7.02") (pin "1") (pinfunction "1_1") (pintype "passive"))
      (node (ref "R7.07") (pin "1") (pinfunction "1_1") (pintype "passive"))
    )
    (net (code "5") (name "ARDUINO.SCL") (class "Default")
      (node (ref "IC3.01") (pin "2") (pinfunction "SCL/SPC_2") (pintype "bidirectional"))
    )
    (net (code "6") (name "ARDUINO.SDA") (class "Default")
      (node (ref "IC3.01") (pin "4") (pinfunction "SDA/SDI/SDO_4") (pintype "bidirectional"))
    )
    (net (code "7") (name "CAR.AUXILLARY") (class "Default")
      (node (ref "U7.2") (pin "2") (pinfunction "G_2") (pintype "passive"))
      (node (ref "X7.02") (pin "IO.10") (pinfunction "IO.10_IO.10") (pintype "bidirectional"))
    )
    (net (code "8") (name "CAR.BLIGHT") (class "Default")
      (node (ref "U7.2") (pin "5") (pinfunction "G_5") (pintype "passive"))
      (node (ref "X7.02") (pin "IO.5") (pinfunction "IO.5_IO.5") (pintype "bidirectional"))
    )
    (net (code "9") (name "CAR.FLIGHT") (class "Default")
      (node (ref "U7.01") (pin "2") (pinfunction "G_2") (pintype "passive"))
      (node (ref "X7.02") (pin "IO.6") (pinfunction "IO.6_IO.6") (pintype "bidirectional"))
    )
    (net (code "10") (name "CAR.GATECTLR") (class "Default")
      (node (ref "U7.01") (pin "5") (pinfunction "G_5") (pintype "passive"))
      (node (ref "X7.02") (pin "IO.9") (pinfunction "IO.9_IO.9") (pintype "bidirectional"))
    )
    (net (code "11") (name "CAR.LAPCNT") (class "Default")
      (node (ref "X7.02") (pin "IO.7") (pinfunction "IO.7_IO.7") (pintype "bidirectional"))
      (node (ref "X7.07") (pin "1") (pinfunction "1_1") (pintype "passive"))
    )
    (net (code "12") (name "CAR.SPEED") (class "Default")
      (node (ref "X7.02") (pin "IO.8") (pinfunction "IO.8_IO.8") (pintype "bidirectional"))
      (node (ref "X7.07") (pin "2") (pinfunction "2_2") (pintype "passive"))
    )
    (net (code "13") (name "GND") (class "Default")
      (node (ref "C1.01") (pin "2") (pinfunction "2_2") (pintype "passive"))
      (node (ref "C1.02") (pin "2") (pinfunction "2_2") (pintype "passive"))
      (node (ref "C1.05") (pin "2") (pinfunction "2_2") (pintype "passive"))
      (node (ref "C1.06") (pin "2") (pinfunction "2_2") (pintype "passive"))
      (node (ref "C2.01") (pin "2") (pinfunction "2_2") (pintype "passive"))
      (node (ref "C2.02") (pin "2") (pinfunction "2_2") (pintype "passive"))
      (node (ref "C2.04") (pin "2") (pinfunction "2_2") (pintype "passive"))
      (node (ref "C2.05") (pin "-") (pinfunction "-_-") (pintype "passive"))
      (node (ref "C3.01") (pin "2") (pinfunction "2_2") (pintype "passive"))
      (node (ref "C3.02") (pin "2") (pinfunction "2_2") (pintype "passive"))
      (node (ref "C3.03") (pin "2") (pinfunction "2_2") (pintype "passive"))
      (node (ref "C3.04") (pin "2") (pinfunction "2_2") (pintype "passive"))
      (node (ref "C3.05") (pin "2") (pinfunction "2_2") (pintype "passive"))
      (node (ref "C4.01") (pin "-") (pinfunction "-_-") (pintype "passive"))
      (node (ref "C4.02") (pin "2") (pinfunction "2_2") (pintype "passive"))
      (node (ref "C4.03") (pin "2") (pinfunction "2_2") (pintype "passive"))
      (node (ref "C4.05") (pin "2") (pinfunction "2_2") (pintype "passive"))
      (node (ref "C6.01") (pin "2") (pinfunction "2_2") (pintype "passive"))
      (node (ref "C6.02") (pin "2") (pinfunction "2_2") (pintype "passive"))
      (node (ref "C6.03") (pin "2") (pinfunction "2_2") (pintype "passive"))
      (node (ref "C6.04") (pin "N") (pinfunction "-_N") (pintype "passive"))
      (node (ref "C6.05") (pin "N") (pinfunction "-_N") (pintype "passive"))
      (node (ref "D7.05") (pin "C") (pinfunction "C_C") (pintype "passive"))
      (node (ref "D7.06") (pin "C") (pinfunction "C_C") (pintype "passive"))
      (node (ref "D7.07") (pin "C") (pinfunction "C_C") (pintype "passive"))
      (node (ref "IC1.01") (pin "4") (pinfunction "GND_4") (pintype "bidirectional"))
      (node (ref "IC1.01") (pin "PAD") (pinfunction "PAD_PAD") (pintype "bidirectional"))
      (node (ref "IC2.00") (pin "20") (pinfunction "AGND_20") (pintype "bidirectional"))
      (node (ref "IC2.00") (pin "21") (pinfunction "PGND_21") (pintype "bidirectional"))
      (node (ref "IC2.00") (pin "22") (pinfunction "PGND_22") (pintype "bidirectional"))
      (node (ref "IC2.00") (pin "PAD") (pinfunction "THERMAL_PAD") (pintype "bidirectional"))
      (node (ref "IC3.01") (pin "14") (pinfunction "RES_14") (pintype "bidirectional"))
      (node (ref "IC3.01") (pin "15") (pinfunction "RES_15") (pintype "bidirectional"))
      (node (ref "IC3.01") (pin "16") (pinfunction "RES_16") (pintype "bidirectional"))
      (node (ref "IC3.01") (pin "17") (pinfunction "RES_17") (pintype "bidirectional"))
      (node (ref "IC3.01") (pin "18") (pinfunction "RES_18") (pintype "bidirectional"))
      (node (ref "IC3.01") (pin "19") (pinfunction "GND_19") (pintype "bidirectional"))
      (node (ref "IC3.01") (pin "20") (pinfunction "GND_20") (pintype "bidirectional"))
      (node (ref "IC4.01") (pin "1") (pinfunction "GND_1") (pintype "bidirectional"))
      (node (ref "IC4.01") (pin "7") (pinfunction "PGND_7") (pintype "bidirectional"))
      (node (ref "IC4.01") (pin "THERMAL") (pinfunction "PAD_THERMAL") (pintype "bidirectional"))
      (node (ref "J4.01") (pin "1") (pinfunction "1_1") (pintype "passive"))
      (node (ref "NTC-") (pin "1") (pinfunction "P_1") (pintype "passive"))
      (node (ref "R1.02") (pin "1") (pinfunction "1_1") (pintype "passive"))
      (node (ref "R1.04") (pin "1") (pinfunction "1_1") (pintype "passive"))
      (node (ref "R2.01") (pin "1") (pinfunction "1_1") (pintype "passive"))
      (node (ref "R2.03") (pin "1") (pinfunction "1_1") (pintype "passive"))
      (node (ref "R2.05") (pin "2") (pinfunction "2_2") (pintype "passive"))
      (node (ref "R2.08") (pin "2") (pinfunction "2_2") (pintype "passive"))
      (node (ref "R2.11") (pin "1") (pinfunction "1_1") (pintype "passive"))
      (node (ref "R2.13") (pin "1") (pinfunction "1_1") (pintype "passive"))
      (node (ref "R2.15") (pin "1") (pinfunction "1_1") (pintype "passive"))
      (node (ref "R3.02") (pin "1") (pinfunction "1_1") (pintype "passive"))
      (node (ref "R3.04") (pin "1") (pinfunction "1_1") (pintype "passive"))
      (node (ref "R3.06") (pin "1") (pinfunction "1_1") (pintype "passive"))
      (node (ref "R4.03") (pin "1") (pinfunction "1_1") (pintype "passive"))
      (node (ref "R4.04") (pin "1") (pinfunction "1_1") (pintype "passive"))
      (node (ref "R4.05") (pin "1") (pinfunction "1_1") (pintype "passive"))
      (node (ref "R6.01") (pin "1") (pinfunction "1_1") (pintype "passive"))
      (node (ref "R7.03") (pin "2") (pinfunction "2_2") (pintype "passive"))
      (node (ref "R7.11") (pin "2") (pinfunction "2_2") (pintype "passive"))
      (node (ref "R7.12") (pin "2") (pinfunction "2_2") (pintype "passive"))
      (node (ref "U6.01") (pin "11") (pinfunction "GND_11") (pintype "passive"))
      (node (ref "U6.01") (pin "3") (pinfunction "PGND_3") (pintype "passive"))
      (node (ref "U6.01") (pin "4") (pinfunction "PGND_2_4") (pintype "passive"))
      (node (ref "U6.01") (pin "5") (pinfunction "PGND_3_5") (pintype "passive"))
      (node (ref "U6.01") (pin "PAD") (pinfunction "EP_PAD") (pintype "passive"))
      (node (ref "U7.01") (pin "1") (pinfunction "S_1") (pintype "passive"))
      (node (ref "U7.01") (pin "4") (pinfunction "S_4") (pintype "passive"))
      (node (ref "U7.03") (pin "1") (pinfunction "S_1") (pintype "passive"))
      (node (ref "U7.03") (pin "4") (pinfunction "S_4") (pintype "passive"))
      (node (ref "U7.2") (pin "1") (pinfunction "S_1") (pintype "passive"))
      (node (ref "U7.2") (pin "4") (pinfunction "S_4") (pintype "passive"))
      (node (ref "X2.01") (pin "2") (pinfunction "2_2") (pintype "passive"))
      (node (ref "X7.02") (pin "GND2") (pinfunction "GND_GND2") (pintype "bidirectional"))
      (node (ref "X7.02") (pin "GND3") (pinfunction "GND_GND3") (pintype "bidirectional"))
      (node (ref "X7.07") (pin "3") (pinfunction "3_3") (pintype "passive"))
      (node (ref "X7.07") (pin "4") (pinfunction "4_4") (pintype "passive"))
    )
    (net (code "14") (name "GND.RAIL") (class "Default")
      (node (ref "R7.12") (pin "1") (pinfunction "1_1") (pintype "passive"))
      (node (ref "X7.01") (pin "1") (pinfunction "1_1") (pintype "passive"))
    )
    (net (code "15") (name "IC2.0.~{CHG}") (class "Default")
      (node (ref "IC2.00") (pin "13") (pinfunction "~{CHG}_13") (pintype "bidirectional"))
      (node (ref "U7.03") (pin "2") (pinfunction "G_2") (pintype "passive"))
    )
    (net (code "16") (name "IC2.0.~{PG}") (class "Default")
      (node (ref "IC2.00") (pin "10") (pinfunction "~{PG}_10") (pintype "bidirectional"))
      (node (ref "U7.03") (pin "5") (pinfunction "G_5") (pintype "passive"))
    )
    (net (code "17") (name "LBO") (class "Default")
      (node (ref "R6.04") (pin "1") (pinfunction "1_1") (pintype "passive"))
      (node (ref "U6.01") (pin "10") (pinfunction "LBO_10") (pintype "output"))
      (node (ref "X7.02") (pin "ADC.0") (pinfunction "ADC.0_ADC.0") (pintype "bidirectional"))
    )
    (net (code "18") (name "MOT.IN1") (class "Default")
      (node (ref "IC4.01") (pin "3") (pinfunction "IN1_3") (pintype "bidirectional"))
      (node (ref "R4.05") (pin "2") (pinfunction "2_2") (pintype "passive"))
      (node (ref "X7.02") (pin "IO.3") (pinfunction "IO.3_IO.3") (pintype "bidirectional"))
    )
    (net (code "19") (name "MOT.IN2") (class "Default")
      (node (ref "IC4.01") (pin "2") (pinfunction "IN2_2") (pintype "bidirectional"))
      (node (ref "R4.04") (pin "2") (pinfunction "2_2") (pintype "passive"))
      (node (ref "X7.02") (pin "IO.4") (pinfunction "IO.4_IO.4") (pintype "bidirectional"))
    )
    (net (code "20") (name "Net-(C1.04-Pad2)") (class "Default")
      (node (ref "C1.04") (pin "2") (pinfunction "2_2") (pintype "passive"))
      (node (ref "R1.02") (pin "2") (pinfunction "2_2") (pintype "passive"))
    )
    (net (code "21") (name "Net-(C1.05-Pad1)") (class "Default")
      (node (ref "C1.05") (pin "1") (pinfunction "1_1") (pintype "passive"))
      (node (ref "C1.06") (pin "1") (pinfunction "1_1") (pintype "passive"))
      (node (ref "FB1.02") (pin "1") (pinfunction "1_1") (pintype "passive"))
      (node (ref "L1.02") (pin "1") (pinfunction "1_1") (pintype "passive"))
      (node (ref "R1.03") (pin "2") (pinfunction "2_2") (pintype "passive"))
    )
    (net (code "22") (name "Net-(C2.03-Pad1)") (class "Default")
      (node (ref "C2.03") (pin "1") (pinfunction "1_1") (pintype "passive"))
      (node (ref "IC2.00") (pin "23") (pinfunction "SW_23") (pintype "bidirectional"))
      (node (ref "IC2.00") (pin "24") (pinfunction "SW_24") (pintype "bidirectional"))
      (node (ref "L2.01") (pin "2") (pinfunction "2_2") (pintype "passive"))
    )
    (net (code "23") (name "Net-(C2.04-Pad1)") (class "Default")
      (node (ref "C2.04") (pin "1") (pinfunction "1_1") (pintype "passive"))
      (node (ref "FB2.01") (pin "1") (pinfunction "1_1") (pintype "passive"))
      (node (ref "IC2.00") (pin "6") (pinfunction "SYS_6") (pintype "bidirectional"))
      (node (ref "IC2.00") (pin "7") (pinfunction "SYS_7") (pintype "bidirectional"))
      (node (ref "L2.01") (pin "1") (pinfunction "1_1") (pintype "passive"))
      (node (ref "Q2.01") (pin "1") (pinfunction "S_1") (pintype "passive"))
      (node (ref "Q2.01") (pin "2") (pinfunction "S_2") (pintype "passive"))
      (node (ref "Q2.01") (pin "3") (pinfunction "S_3") (pintype "passive"))
    )
    (net (code "24") (name "Net-(C6.04-+)") (class "Default")
      (node (ref "C6.03") (pin "1") (pinfunction "1_1") (pintype "passive"))
      (node (ref "C6.04") (pin "P") (pinfunction "+_P") (pintype "passive"))
      (node (ref "C6.05") (pin "P") (pinfunction "+_P") (pintype "passive"))
      (node (ref "FB6.01") (pin "1") (pinfunction "1_1") (pintype "passive"))
      (node (ref "U6.01") (pin "13") (pinfunction "VOUT_13") (pintype "output"))
      (node (ref "U6.01") (pin "14") (pinfunction "VOUT_2_14") (pintype "output"))
      (node (ref "U6.01") (pin "15") (pinfunction "VOUT_3_15") (pintype "output"))
    )
    (net (code "25") (name "Net-(D7.03-PadA)") (class "Default")
      (node (ref "D7.03") (pin "A") (pinfunction "A_A") (pintype "passive"))
      (node (ref "R7,01") (pin "1") (pinfunction "1_1") (pintype "passive"))
    )
    (net (code "26") (name "Net-(D7.04-PadA)") (class "Default")
      (node (ref "D7.04") (pin "A") (pinfunction "A_A") (pintype "passive"))
      (node (ref "R7.01") (pin "1") (pinfunction "1_1") (pintype "passive"))
    )
    (net (code "27") (name "Net-(D7.05-PadA)") (class "Default")
      (node (ref "D7.05") (pin "A") (pinfunction "A_A") (pintype "passive"))
      (node (ref "R7,02") (pin "1") (pinfunction "1_1") (pintype "passive"))
    )
    (net (code "28") (name "Net-(D7.06-PadA)") (class "Default")
      (node (ref "D7.06") (pin "A") (pinfunction "A_A") (pintype "passive"))
      (node (ref "R7,04") (pin "1") (pinfunction "1_1") (pintype "passive"))
    )
    (net (code "29") (name "Net-(D7.07-PadA)") (class "Default")
      (node (ref "D7.07") (pin "A") (pinfunction "A_A") (pintype "passive"))
      (node (ref "R7,05") (pin "1") (pinfunction "1_1") (pintype "passive"))
    )
    (net (code "30") (name "Net-(F1.01-Pad2)") (class "Default")
      (node (ref "F1.01") (pin "2") (pinfunction "2_2") (pintype "passive"))
      (node (ref "FB1.01") (pin "1") (pinfunction "1_1") (pintype "passive"))
    )
    (net (code "31") (name "Net-(FB1.02-Pad2)") (class "Default")
      (node (ref "FB1.02") (pin "2") (pinfunction "2_2") (pintype "passive"))
      (node (ref "R1.05") (pin "2") (pinfunction "2_2") (pintype "passive"))
      (node (ref "R1.06") (pin "1") (pinfunction "1_1") (pintype "passive"))
    )
    (net (code "32") (name "Net-(FB2.01-Pad2)") (class "Default")
      (node (ref "FB2.01") (pin "2") (pinfunction "2_2") (pintype "passive"))
      (node (ref "R2.07") (pin "2") (pinfunction "2_2") (pintype "passive"))
    )
    (net (code "33") (name "Net-(FB6.01-Pad2)") (class "Default")
      (node (ref "FB6.01") (pin "2") (pinfunction "2_2") (pintype "passive"))
      (node (ref "R6.03") (pin "2") (pinfunction "2_2") (pintype "passive"))
    )
    (net (code "34") (name "Net-(IC1.01-BOOT)") (class "Default")
      (node (ref "C1.03") (pin "1") (pinfunction "1_1") (pintype "passive"))
      (node (ref "IC1.01") (pin "1") (pinfunction "BOOT_1") (pintype "bidirectional"))
    )
    (net (code "35") (name "Net-(IC1.01-COMP)") (class "Default")
      (node (ref "C1.04") (pin "1") (pinfunction "1_1") (pintype "passive"))
      (node (ref "IC1.01") (pin "6") (pinfunction "COMP_6") (pintype "bidirectional"))
    )
    (net (code "36") (name "Net-(IC1.01-EN)") (class "Default")
      (node (ref "IC1.01") (pin "7") (pinfunction "EN_7") (pintype "bidirectional"))
      (node (ref "R1.01") (pin "2") (pinfunction "2_2") (pintype "passive"))
    )
    (net (code "37") (name "Net-(IC1.01-FB)") (class "Default")
      (node (ref "IC1.01") (pin "5") (pinfunction "FB_5") (pintype "bidirectional"))
      (node (ref "R1.03") (pin "1") (pinfunction "1_1") (pintype "passive"))
      (node (ref "R1.04") (pin "2") (pinfunction "2_2") (pintype "passive"))
    )
    (net (code "38") (name "Net-(IC1.01-SS)") (class "Default")
      (node (ref "C1.02") (pin "1") (pinfunction "1_1") (pintype "passive"))
      (node (ref "IC1.01") (pin "8") (pinfunction "SS_8") (pintype "bidirectional"))
    )
    (net (code "39") (name "Net-(IC1.01-SW)") (class "Default")
      (node (ref "C1.03") (pin "2") (pinfunction "2_2") (pintype "passive"))
      (node (ref "IC1.01") (pin "3") (pinfunction "SW_3") (pintype "bidirectional"))
      (node (ref "L1.02") (pin "2") (pinfunction "2_2") (pintype "passive"))
    )
    (net (code "40") (name "Net-(IC1.01-VIN)") (class "Default")
      (node (ref "C1.01") (pin "1") (pinfunction "1_1") (pintype "passive"))
      (node (ref "FB1.01") (pin "2") (pinfunction "2_2") (pintype "passive"))
      (node (ref "IC1.01") (pin "2") (pinfunction "VIN_2") (pintype "bidirectional"))
      (node (ref "R1.01") (pin "1") (pinfunction "1_1") (pintype "passive"))
    )
    (net (code "41") (name "Net-(IC2.00B-BGATE)") (class "Default")
      (node (ref "IC2.00") (pin "11") (pinfunction "BGATE_11") (pintype "bidirectional"))
      (node (ref "Q2.01") (pin "4") (pinfunction "G_4") (pintype "passive"))
    )
    (net (code "42") (name "Net-(IC2.00B-BOOT)") (class "Default")
      (node (ref "C2.03") (pin "2") (pinfunction "2_2") (pintype "passive"))
      (node (ref "IC2.00") (pin "2") (pinfunction "BOOT_2") (pintype "bidirectional"))
    )
    (net (code "43") (name "Net-(IC2.00B-ISET)") (class "Default")
      (node (ref "IC2.00") (pin "12") (pinfunction "ISET_12") (pintype "bidirectional"))
      (node (ref "R2.03") (pin "2") (pinfunction "2_2") (pintype "passive"))
    )
    (net (code "44") (name "Net-(IC2.00B-IUSB-Pad14)") (class "Default")
      (node (ref "IC2.00") (pin "14") (pinfunction "IUSB_14") (pintype "bidirectional"))
      (node (ref "R2.14") (pin "1") (pinfunction "1_1") (pintype "passive"))
      (node (ref "R2.15") (pin "2") (pinfunction "2_2") (pintype "passive"))
    )
    (net (code "45") (name "Net-(IC2.00B-IUSB-Pad16)") (class "Default")
      (node (ref "IC2.00") (pin "16") (pinfunction "IUSB_16") (pintype "bidirectional"))
      (node (ref "R2.12") (pin "1") (pinfunction "1_1") (pintype "passive"))
      (node (ref "R2.13") (pin "2") (pinfunction "2_2") (pintype "passive"))
    )
    (net (code "46") (name "Net-(IC2.00B-IUSB-Pad17)") (class "Default")
      (node (ref "IC2.00") (pin "17") (pinfunction "IUSB_17") (pintype "bidirectional"))
      (node (ref "R2.10") (pin "1") (pinfunction "1_1") (pintype "passive"))
      (node (ref "R2.11") (pin "2") (pinfunction "2_2") (pintype "passive"))
    )
    (net (code "47") (name "Net-(IC2.00B-PMID)") (class "Default")
      (node (ref "C2.01") (pin "1") (pinfunction "1_1") (pintype "passive"))
      (node (ref "IC2.00") (pin "1") (pinfunction "PMID_1") (pintype "bidirectional"))
    )
    (net (code "48") (name "Net-(IC2.00B-TS)") (class "Default")
      (node (ref "IC2.00") (pin "5") (pinfunction "TS_5") (pintype "bidirectional"))
      (node (ref "NTC+") (pin "1") (pinfunction "P_1") (pintype "passive"))
      (node (ref "R2.04") (pin "2") (pinfunction "2_2") (pintype "passive"))
      (node (ref "R2.05") (pin "1") (pinfunction "1_1") (pintype "passive"))
      (node (ref "R2.08") (pin "1") (pinfunction "1_1") (pintype "passive"))
    )
    (net (code "49") (name "Net-(IC2.00B-VDPM)") (class "Default")
      (node (ref "IC2.00") (pin "15") (pinfunction "VDPM_15") (pintype "bidirectional"))
      (node (ref "R2.01") (pin "2") (pinfunction "2_2") (pintype "passive"))
      (node (ref "R2.02") (pin "1") (pinfunction "1_1") (pintype "passive"))
    )
    (net (code "50") (name "Net-(IC3.01-C1)") (class "Default")
      (node (ref "C3.02") (pin "1") (pinfunction "1_1") (pintype "passive"))
      (node (ref "IC3.01") (pin "24") (pinfunction "C1_24") (pintype "bidirectional"))
    )
    (net (code "51") (name "Net-(IC3.01-CAP)") (class "Default")
      (node (ref "C3.01") (pin "1") (pinfunction "1_1") (pintype "passive"))
      (node (ref "IC3.01") (pin "21") (pinfunction "CAP_21") (pintype "bidirectional"))
    )
    (net (code "52") (name "Net-(IC3.01-CS_A{slash}G)") (class "Default")
      (node (ref "IC3.01") (pin "7") (pinfunction "CS_A/G_7") (pintype "bidirectional"))
      (node (ref "R3.07") (pin "1") (pinfunction "1_1") (pintype "passive"))
    )
    (net (code "53") (name "Net-(IC3.01-CS_M)") (class "Default")
      (node (ref "IC3.01") (pin "8") (pinfunction "CS_M_8") (pintype "bidirectional"))
      (node (ref "R3.08") (pin "1") (pinfunction "1_1") (pintype "passive"))
    )
    (net (code "54") (name "Net-(IC3.01-DEN_A{slash}G)") (class "Default")
      (node (ref "IC3.01") (pin "13") (pinfunction "DEN_A/G_13") (pintype "bidirectional"))
      (node (ref "R3.01") (pin "1") (pinfunction "1_1") (pintype "passive"))
      (node (ref "R3.02") (pin "2") (pinfunction "2_2") (pintype "passive"))
    )
    (net (code "55") (name "Net-(IC3.01-SDO_A{slash}G)") (class "Default")
      (node (ref "IC3.01") (pin "5") (pinfunction "SDO_A/G_5") (pintype "bidirectional"))
      (node (ref "R3.03") (pin "1") (pinfunction "1_1") (pintype "passive"))
      (node (ref "R3.04") (pin "2") (pinfunction "2_2") (pintype "passive"))
    )
    (net (code "56") (name "Net-(IC3.01-SDO_M)") (class "Default")
      (node (ref "IC3.01") (pin "6") (pinfunction "SDO_M_6") (pintype "bidirectional"))
      (node (ref "R3.05") (pin "1") (pinfunction "1_1") (pintype "passive"))
      (node (ref "R3.06") (pin "2") (pinfunction "2_2") (pintype "passive"))
    )
    (net (code "57") (name "Net-(IC4.01-ILIM)") (class "Default")
      (node (ref "IC4.01") (pin "4") (pinfunction "ILIM_4") (pintype "bidirectional"))
      (node (ref "R4.03") (pin "2") (pinfunction "2_2") (pintype "passive"))
    )
    (net (code "58") (name "Net-(IC4.01-OUT1)") (class "Default")
      (node (ref "C4.04") (pin "2") (pinfunction "2_2") (pintype "passive"))
      (node (ref "C4.05") (pin "1") (pinfunction "1_1") (pintype "passive"))
      (node (ref "IC4.01") (pin "6") (pinfunction "OUT1_6") (pintype "bidirectional"))
      (node (ref "X7.05") (pin "1") (pinfunction "1_1") (pintype "passive"))
    )
    (net (code "59") (name "Net-(IC4.01-OUT2)") (class "Default")
      (node (ref "IC4.01") (pin "8") (pinfunction "OUT2_8") (pintype "bidirectional"))
      (node (ref "J4.01") (pin "3") (pinfunction "3_3") (pintype "passive"))
    )
    (net (code "60") (name "Net-(IC4.01-VM)") (class "Default")
      (node (ref "C4.01") (pin "+") (pinfunction "+_+") (pintype "passive"))
      (node (ref "C4.02") (pin "1") (pinfunction "1_1") (pintype "passive"))
      (node (ref "C4.04") (pin "1") (pinfunction "1_1") (pintype "passive"))
      (node (ref "FB4.01") (pin "1") (pinfunction "1_1") (pintype "passive"))
      (node (ref "IC4.01") (pin "5") (pinfunction "VM_5") (pintype "bidirectional"))
    )
    (net (code "61") (name "Net-(R7.04-Pad2)") (class "Default")
      (node (ref "R7.04") (pin "2") (pinfunction "2_2") (pintype "passive"))
      (node (ref "X7.08") (pin "1") (pinfunction "1_1") (pintype "bidirectional"))
    )
    (net (code "62") (name "Net-(R7.06-Pad2)") (class "Default")
      (node (ref "R7.06") (pin "2") (pinfunction "2_2") (pintype "passive"))
      (node (ref "X7.02") (pin "5V") (pinfunction "5V_5V") (pintype "bidirectional"))
    )
    (net (code "63") (name "Net-(R7.07-Pad2)") (class "Default")
      (node (ref "R7.07") (pin "2") (pinfunction "2_2") (pintype "passive"))
      (node (ref "X7.02") (pin "VIN") (pinfunction "VIN_VIN") (pintype "bidirectional"))
    )
    (net (code "64") (name "Net-(R7.08-Pad2)") (class "Default")
      (node (ref "R7.08") (pin "2") (pinfunction "2_2") (pintype "passive"))
      (node (ref "X7.11") (pin "2") (pinfunction "2_2") (pintype "bidirectional"))
    )
    (net (code "65") (name "Net-(R7.09-Pad2)") (class "Default")
      (node (ref "R7.09") (pin "2") (pinfunction "2_2") (pintype "passive"))
      (node (ref "X7.06") (pin "1") (pinfunction "1_1") (pintype "bidirectional"))
    )
    (net (code "66") (name "Net-(R7.10-Pad2)") (class "Default")
      (node (ref "R7.10") (pin "2") (pinfunction "2_2") (pintype "passive"))
      (node (ref "X7.03") (pin "2") (pinfunction "2_2") (pintype "bidirectional"))
    )
    (net (code "67") (name "Net-(U6.01-EN)") (class "Default")
      (node (ref "R6.05") (pin "1") (pinfunction "1_1") (pintype "passive"))
      (node (ref "U6.01") (pin "9") (pinfunction "EN_9") (pintype "input"))
    )
    (net (code "68") (name "Net-(U6.01-LBI)") (class "Default")
      (node (ref "R6.01") (pin "2") (pinfunction "2_2") (pintype "passive"))
      (node (ref "U6.01") (pin "7") (pinfunction "LBI_7") (pintype "input"))
    )
    (net (code "69") (name "Net-(U6.01-SW)") (class "Default")
      (node (ref "L6.01") (pin "2") (pinfunction "2_2") (pintype "passive"))
      (node (ref "U6.01") (pin "1") (pinfunction "SW_1") (pintype "input"))
      (node (ref "U6.01") (pin "2") (pinfunction "SW_2_2") (pintype "input"))
    )
    (net (code "70") (name "Net-(U6.01-SYNC)") (class "Default")
      (node (ref "R6.02") (pin "2") (pinfunction "2_2") (pintype "passive"))
      (node (ref "U6.01") (pin "8") (pinfunction "SYNC_8") (pintype "input"))
    )
    (net (code "71") (name "Net-(U7.01A-D)") (class "Default")
      (node (ref "R7.04") (pin "1") (pinfunction "1_1") (pintype "passive"))
      (node (ref "U7.01") (pin "6") (pinfunction "D_6") (pintype "passive"))
    )
    (net (code "72") (name "Net-(U7.01B-D)") (class "Default")
      (node (ref "R7.08") (pin "1") (pinfunction "1_1") (pintype "passive"))
      (node (ref "U7.01") (pin "3") (pinfunction "D_3") (pintype "passive"))
    )
    (net (code "73") (name "Net-(U7.2A-D)") (class "Default")
      (node (ref "R7.10") (pin "1") (pinfunction "1_1") (pintype "passive"))
      (node (ref "U7.2") (pin "6") (pinfunction "D_6") (pintype "passive"))
    )
    (net (code "74") (name "Net-(U7.2B-D)") (class "Default")
      (node (ref "R7.09") (pin "1") (pinfunction "1_1") (pintype "passive"))
      (node (ref "U7.2") (pin "3") (pinfunction "D_3") (pintype "passive"))
    )
    (net (code "75") (name "Net-(U7.03A-D)") (class "Default")
      (node (ref "D7.03") (pin "C") (pinfunction "C_C") (pintype "passive"))
      (node (ref "U7.03") (pin "6") (pinfunction "D_6") (pintype "passive"))
    )
    (net (code "76") (name "Net-(U7.03B-D)") (class "Default")
      (node (ref "D7.04") (pin "C") (pinfunction "C_C") (pintype "passive"))
      (node (ref "U7.03") (pin "3") (pinfunction "D_3") (pintype "passive"))
    )
    (net (code "77") (name "Net-(X7.02B-3V3)") (class "Default")
      (node (ref "R7.05") (pin "2") (pinfunction "2_2") (pintype "passive"))
      (node (ref "X7.02") (pin "3.3V") (pinfunction "3V3_3.3V") (pintype "bidirectional"))
    )
    (net (code "78") (name "Net-(X7.03-Pad1)") (class "Default")
      (node (ref "X7.03") (pin "1") (pinfunction "1_1") (pintype "bidirectional"))
      (node (ref "X7.06") (pin "2") (pinfunction "2_2") (pintype "bidirectional"))
      (node (ref "X7.09") (pin "2") (pinfunction "2_2") (pintype "passive"))
    )
    (net (code "79") (name "Net-(X7.04B-1)") (class "Default")
      (node (ref "R7.11") (pin "1") (pinfunction "1_1") (pintype "passive"))
      (node (ref "X7.04") (pin "2") (pinfunction "1_2") (pintype "passive"))
    )
    (net (code "80") (name "Net-(X7.05B-1)") (class "Default")
      (node (ref "J4.01") (pin "2") (pinfunction "2_2") (pintype "passive"))
      (node (ref "X7.05") (pin "2") (pinfunction "1_2") (pintype "passive"))
    )
    (net (code "81") (name "Net-(X7.08-Pad2)") (class "Default")
      (node (ref "X7.08") (pin "2") (pinfunction "2_2") (pintype "bidirectional"))
      (node (ref "X7.10") (pin "2") (pinfunction "2_2") (pintype "passive"))
      (node (ref "X7.11") (pin "1") (pinfunction "1_1") (pintype "bidirectional"))
    )
    (net (code "82") (name "RAILS.RX") (class "Default")
      (node (ref "R7.02") (pin "2") (pinfunction "2_2") (pintype "passive"))
      (node (ref "R7.03") (pin "1") (pinfunction "1_1") (pintype "passive"))
      (node (ref "X7.02") (pin "IO.0") (pinfunction "IO.0_IO.0") (pintype "bidirectional"))
    )
    (net (code "83") (name "SCL") (class "Default")
      (node (ref "X7.02") (pin "SCL") (pinfunction "SCL_SCL") (pintype "bidirectional"))
    )
    (net (code "84") (name "SDA") (class "Default")
      (node (ref "X7.02") (pin "SDA") (pinfunction "SDA_SDA") (pintype "bidirectional"))
    )
    (net (code "85") (name "V+") (class "Default")
      (node (ref "C2.02") (pin "1") (pinfunction "1_1") (pintype "passive"))
      (node (ref "IC2.00") (pin "3") (pinfunction "DRV_3") (pintype "bidirectional"))
      (node (ref "R2.04") (pin "1") (pinfunction "1_1") (pintype "passive"))
    )
    (net (code "86") (name "VCC{slash}2") (class "Default")
      (node (ref "D1.01") (pin "A") (pinfunction "A_A") (pintype "passive"))
      (node (ref "X7.01") (pin "2") (pinfunction "1_2") (pintype "passive"))
    )
    (net (code "87") (name "unconnected-(IC2.00B-~{CE}-Pad4)") (class "Default")
      (node (ref "IC2.00") (pin "4") (pinfunction "~{CE}_4") (pintype "bidirectional"))
    )
    (net (code "88") (name "unconnected-(IC3.01-DRDY_M-Pad9)") (class "Default")
      (node (ref "IC3.01") (pin "9") (pinfunction "DRDY_M_9") (pintype "bidirectional"))
    )
    (net (code "89") (name "unconnected-(IC3.01-INT2_A{slash}G-Pad12)") (class "Default")
      (node (ref "IC3.01") (pin "12") (pinfunction "INT2_A/G_12") (pintype "bidirectional"))
    )
    (net (code "90") (name "unconnected-(IC3.01-INT_M-Pad10)") (class "Default")
      (node (ref "IC3.01") (pin "10") (pinfunction "INT_M_10") (pintype "bidirectional"))
    )
    (net (code "91") (name "unconnected-(L2-Pad1)") (class "Default")
      (node (ref "L2") (pin "1") (pinfunction "1_1") (pintype "passive"))
    )
    (net (code "92") (name "unconnected-(L2-Pad2)") (class "Default")
      (node (ref "L2") (pin "2") (pinfunction "2_2") (pintype "passive"))
    )
    (net (code "93") (name "unconnected-(U6.01-FB-Pad12)") (class "Default")
      (node (ref "U6.01") (pin "12") (pinfunction "FB_12") (pintype "input"))
    )
    (net (code "94") (name "unconnected-(U6.01-NC-Pad16)") (class "Default")
      (node (ref "U6.01") (pin "16") (pinfunction "NC_16") (pintype "no_connect"))
    )
    (net (code "95") (name "unconnected-(X7.02-PadADC.1)") (class "Default")
      (node (ref "X7.02") (pin "ADC.1") (pinfunction "ADC.1_ADC.1") (pintype "bidirectional"))
    )
    (net (code "96") (name "unconnected-(X7.02-PadADC.2)") (class "Default")
      (node (ref "X7.02") (pin "ADC.2") (pinfunction "ADC.2_ADC.2") (pintype "bidirectional"))
    )
    (net (code "97") (name "unconnected-(X7.02-PadADC.3)") (class "Default")
      (node (ref "X7.02") (pin "ADC.3") (pinfunction "ADC.3_ADC.3") (pintype "bidirectional"))
    )
    (net (code "98") (name "unconnected-(X7.02-PadADC.4)") (class "Default")
      (node (ref "X7.02") (pin "ADC.4") (pinfunction "ADC.4_ADC.4") (pintype "bidirectional"))
    )
    (net (code "99") (name "unconnected-(X7.02-PadADC.5)") (class "Default")
      (node (ref "X7.02") (pin "ADC.5") (pinfunction "ADC.5_ADC.5") (pintype "bidirectional"))
    )
    (net (code "100") (name "unconnected-(X7.02-PadAREF)") (class "Default")
      (node (ref "X7.02") (pin "AREF") (pinfunction "AREF_AREF") (pintype "bidirectional"))
    )
    (net (code "101") (name "unconnected-(X7.02-PadIO.1)") (class "Default")
      (node (ref "X7.02") (pin "IO.1") (pinfunction "IO.1_IO.1") (pintype "bidirectional"))
    )
    (net (code "102") (name "unconnected-(X7.02-PadIO.11)") (class "Default")
      (node (ref "X7.02") (pin "IO.11") (pinfunction "IO.11_IO.11") (pintype "bidirectional"))
    )
    (net (code "103") (name "unconnected-(X7.02-PadIO.12)") (class "Default")
      (node (ref "X7.02") (pin "IO.12") (pinfunction "IO.12_IO.12") (pintype "bidirectional"))
    )
    (net (code "104") (name "unconnected-(X7.02-PadIO.13)") (class "Default")
      (node (ref "X7.02") (pin "IO.13") (pinfunction "IO.13_IO.13") (pintype "bidirectional"))
    )
    (net (code "105") (name "unconnected-(X7.02-PadN{slash}C)") (class "Default")
      (node (ref "X7.02") (pin "N/C") (pinfunction "N/C_N/C") (pintype "bidirectional"))
    )
    (net (code "106") (name "unconnected-(X7.02-PadRESET)") (class "Default")
      (node (ref "X7.02") (pin "RESET") (pinfunction "RESET_RESET") (pintype "bidirectional"))
    )
    (net (code "107") (name "unconnected-(X7.02B-IOREF-PadI{slash}OREF)") (class "Default")
      (node (ref "X7.02") (pin "I/OREF") (pinfunction "IOREF_I/OREF") (pintype "bidirectional"))
    )
    (net (code "108") (name "unconnected-(X7.02D-GND-PadGND.1)") (class "Default")
      (node (ref "X7.02") (pin "GND.1") (pinfunction "GND_GND.1") (pintype "bidirectional"))
    )
    (net (code "109") (name "~{IRQ_GYRO}") (class "Default")
      (node (ref "IC3.01") (pin "11") (pinfunction "INT1_A/G_11") (pintype "bidirectional"))
      (node (ref "X7.02") (pin "IO.2") (pinfunction "IO.2_IO.2") (pintype "bidirectional"))
    )
  )
)
